# DDR3_LoongSon.net
KiCad netlist of a schematic drawn in Altium Designer
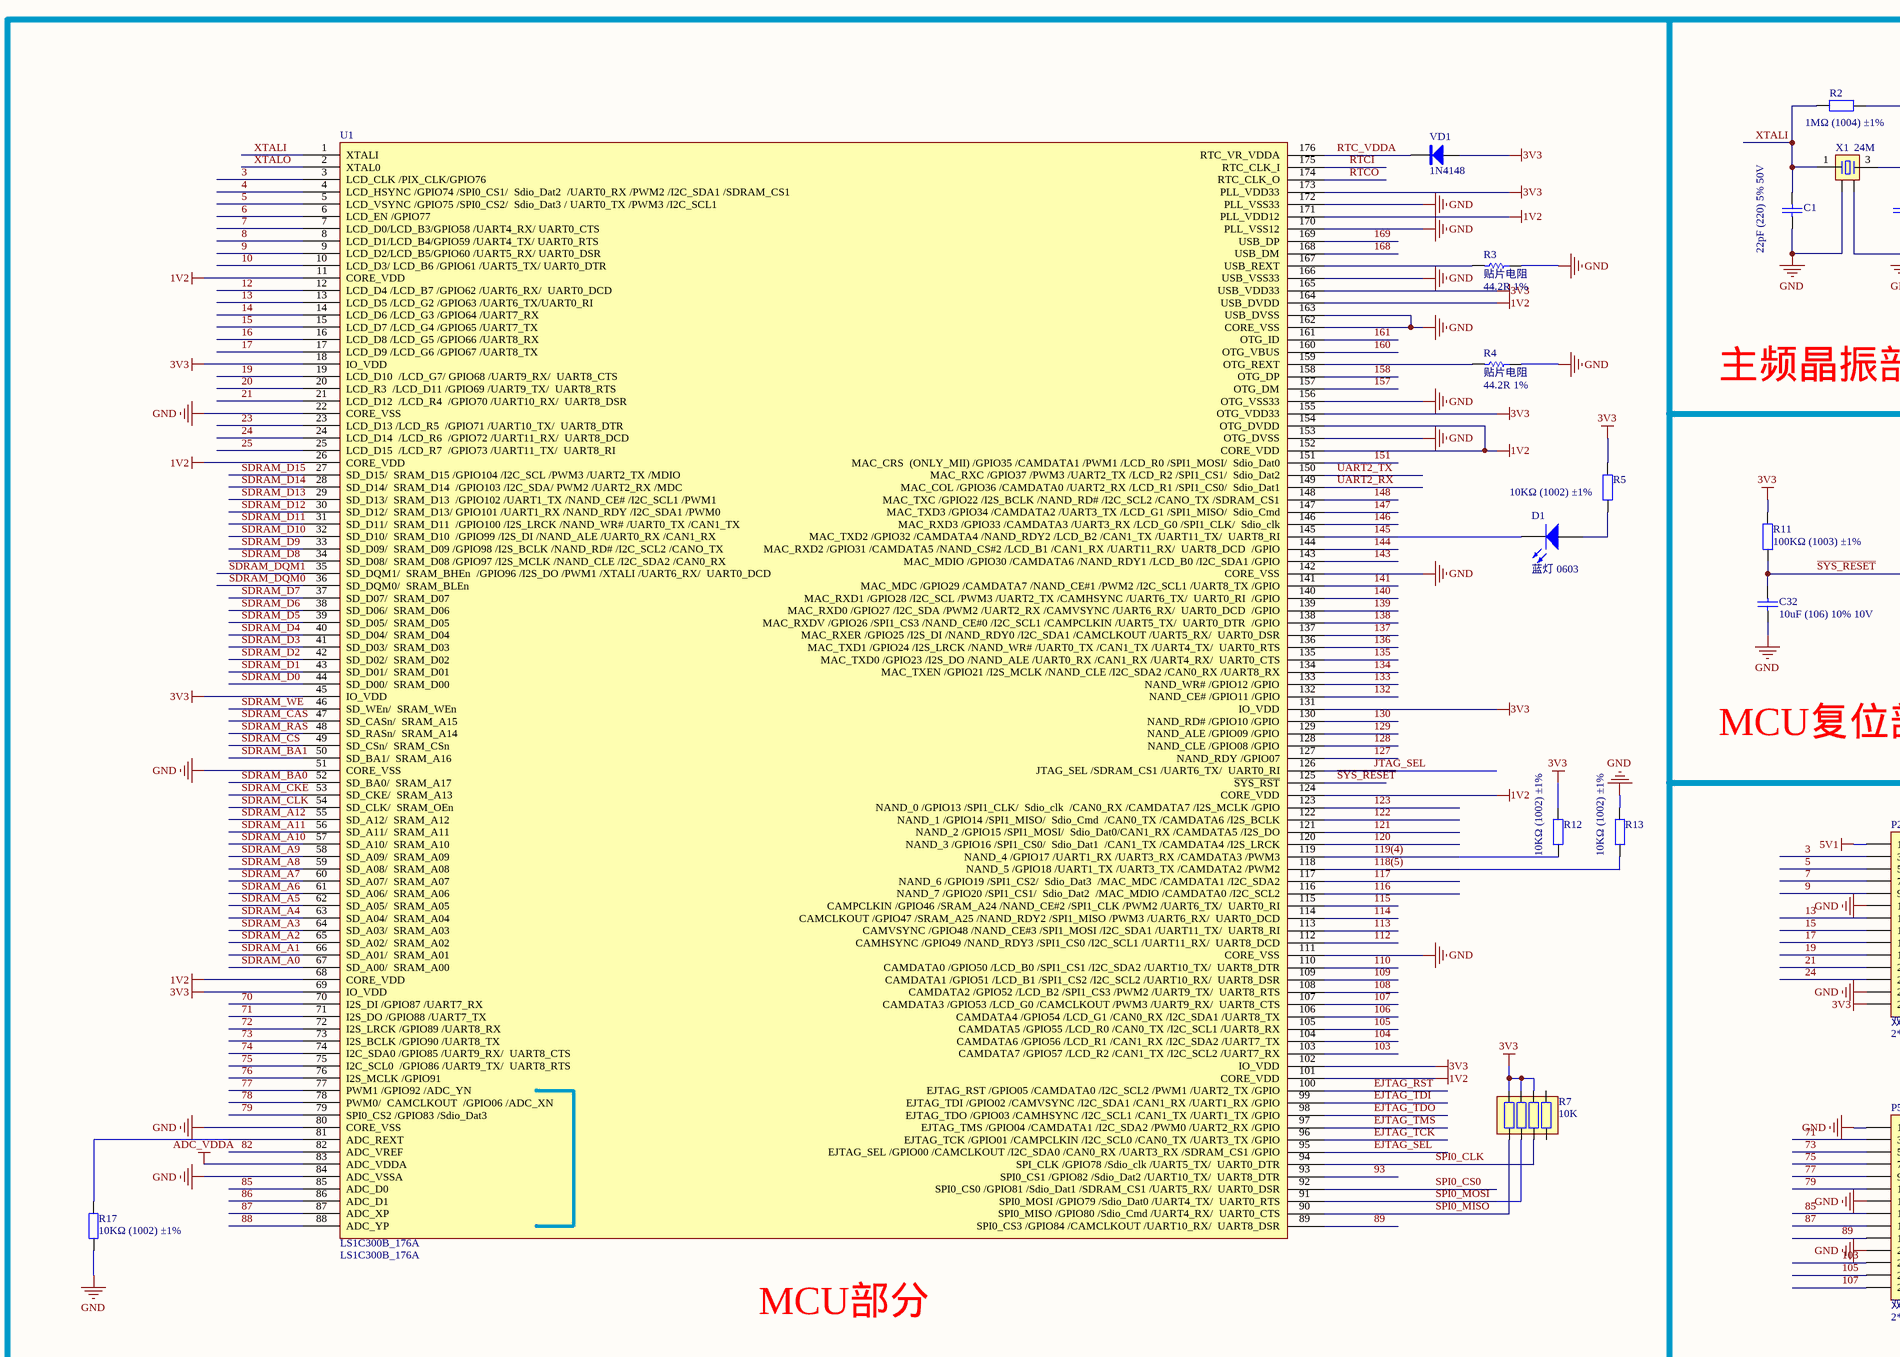
[diagram p0: DDR3_LoongSon.SchDoc, top left]
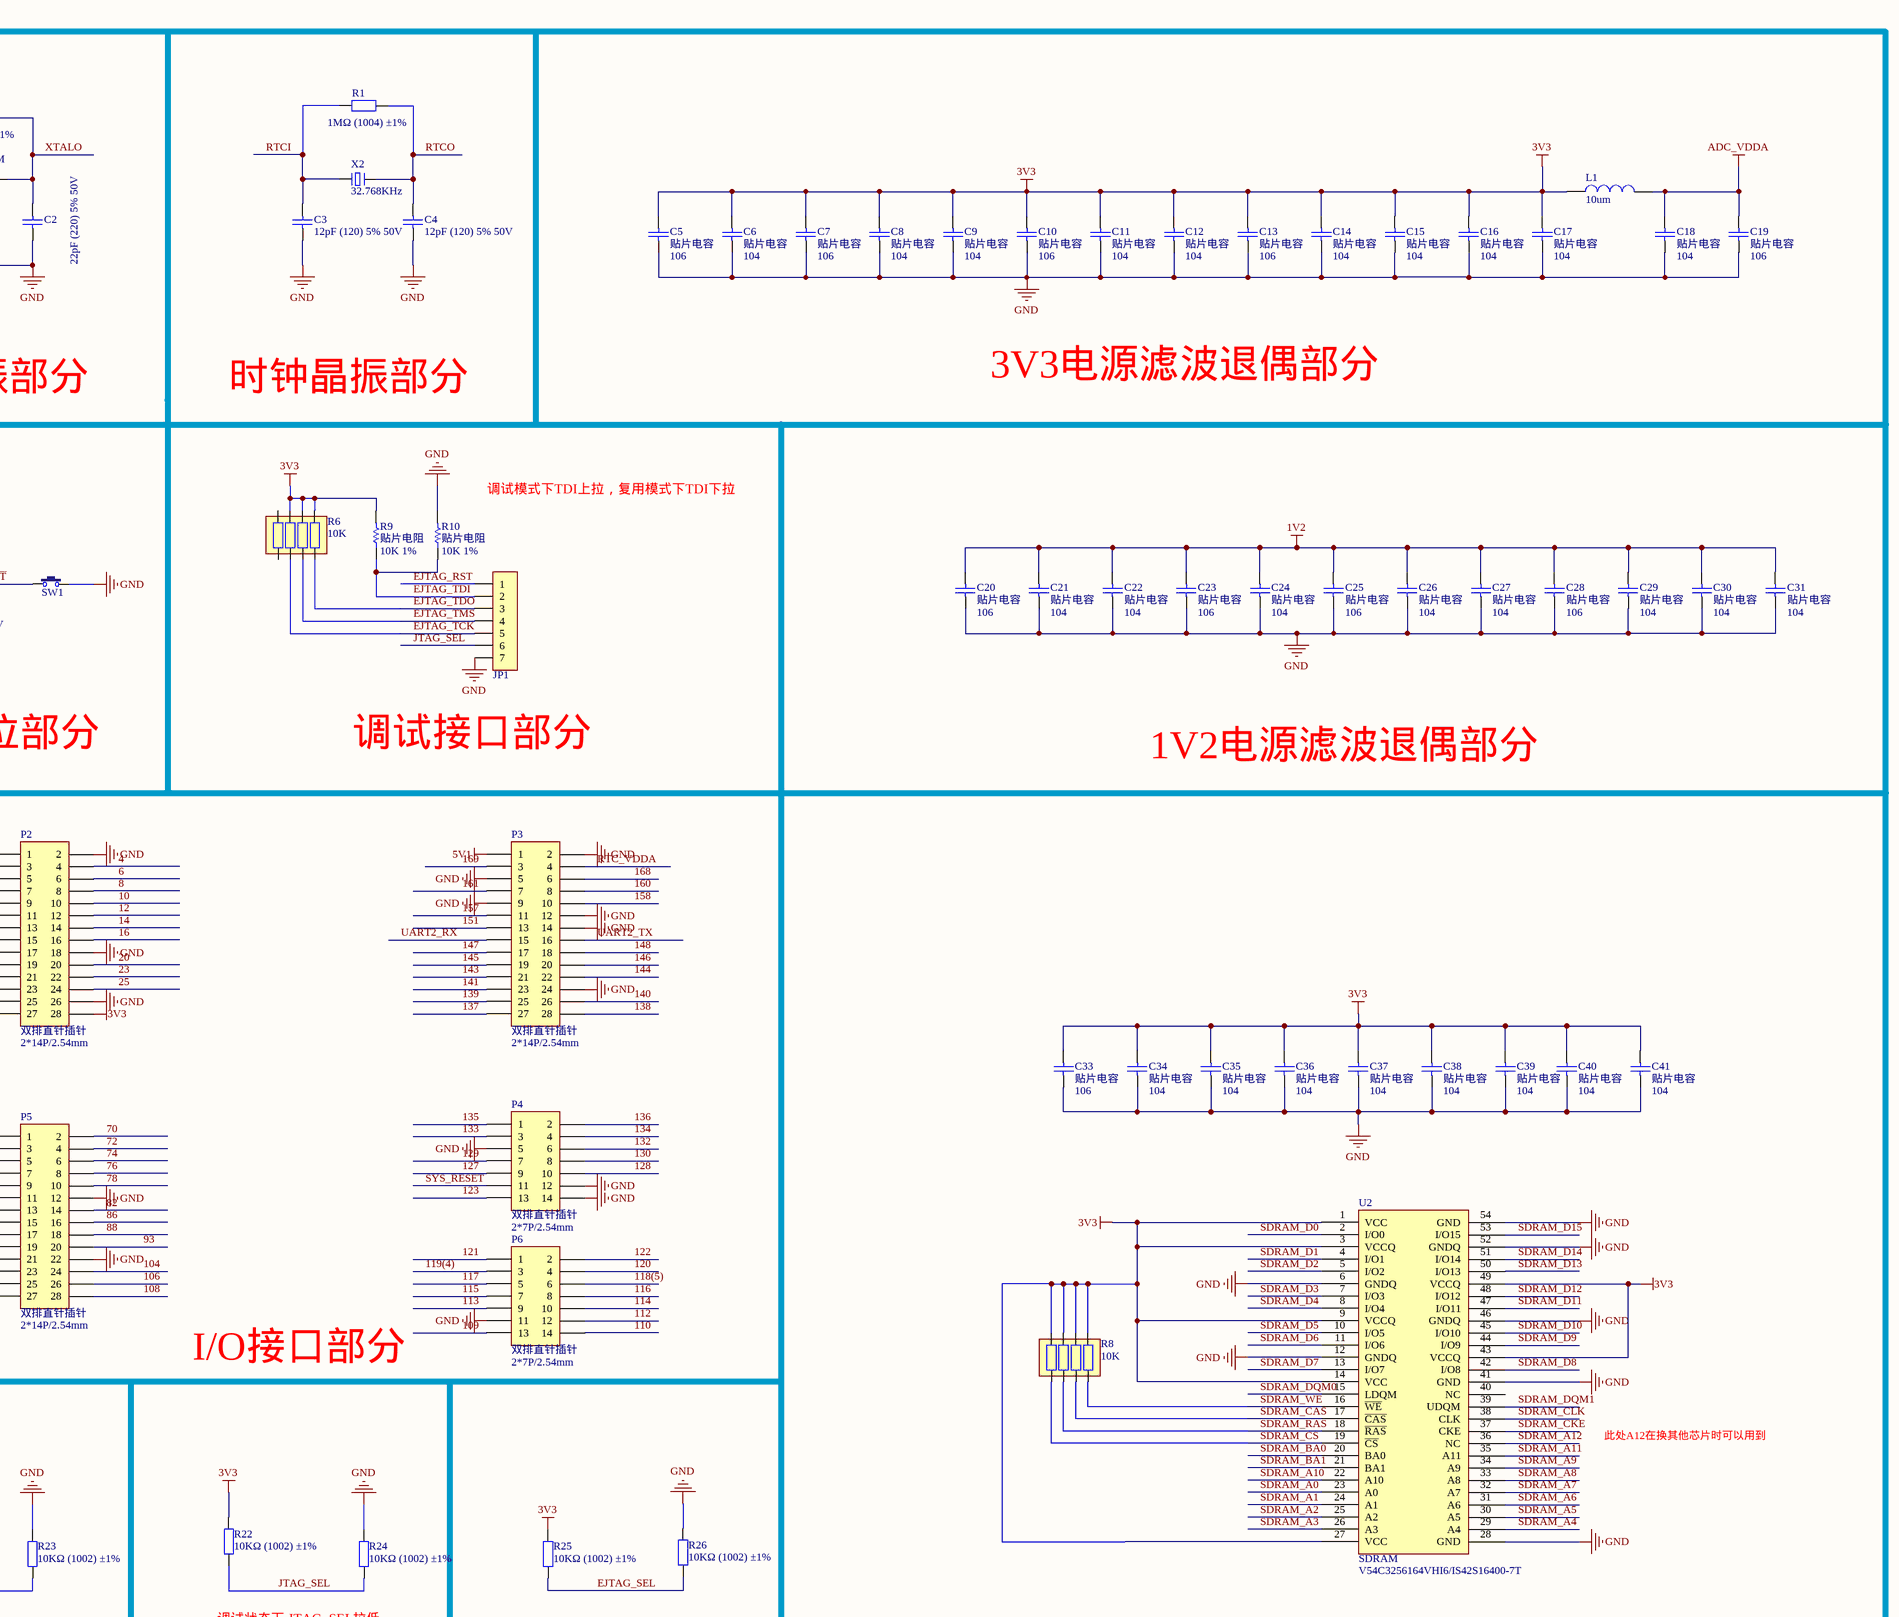
[diagram p1: DDR3_LoongSon.SchDoc, top right]
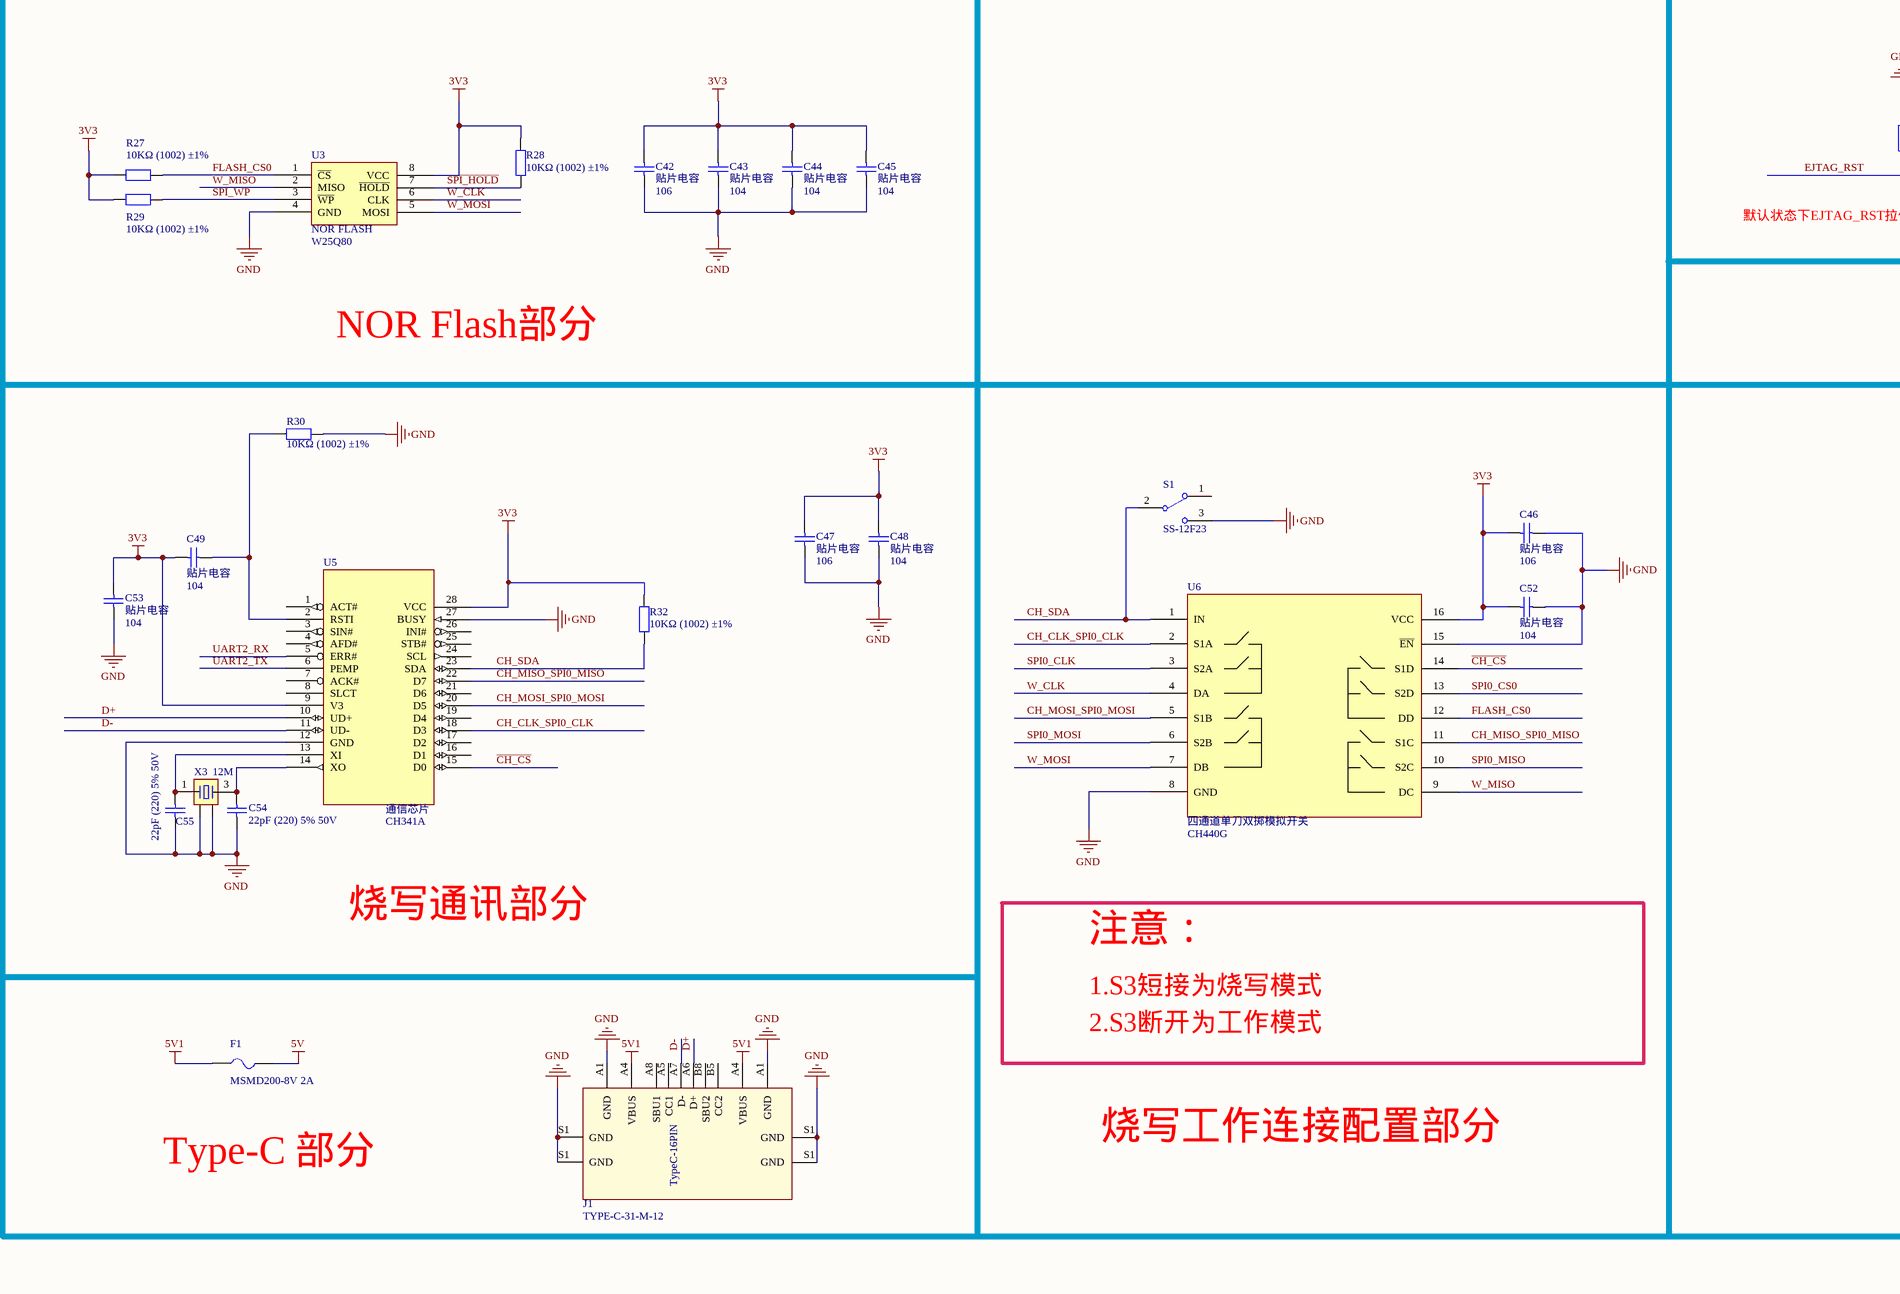
[diagram p2: DDR3_LoongSon.SchDoc, bottom left]
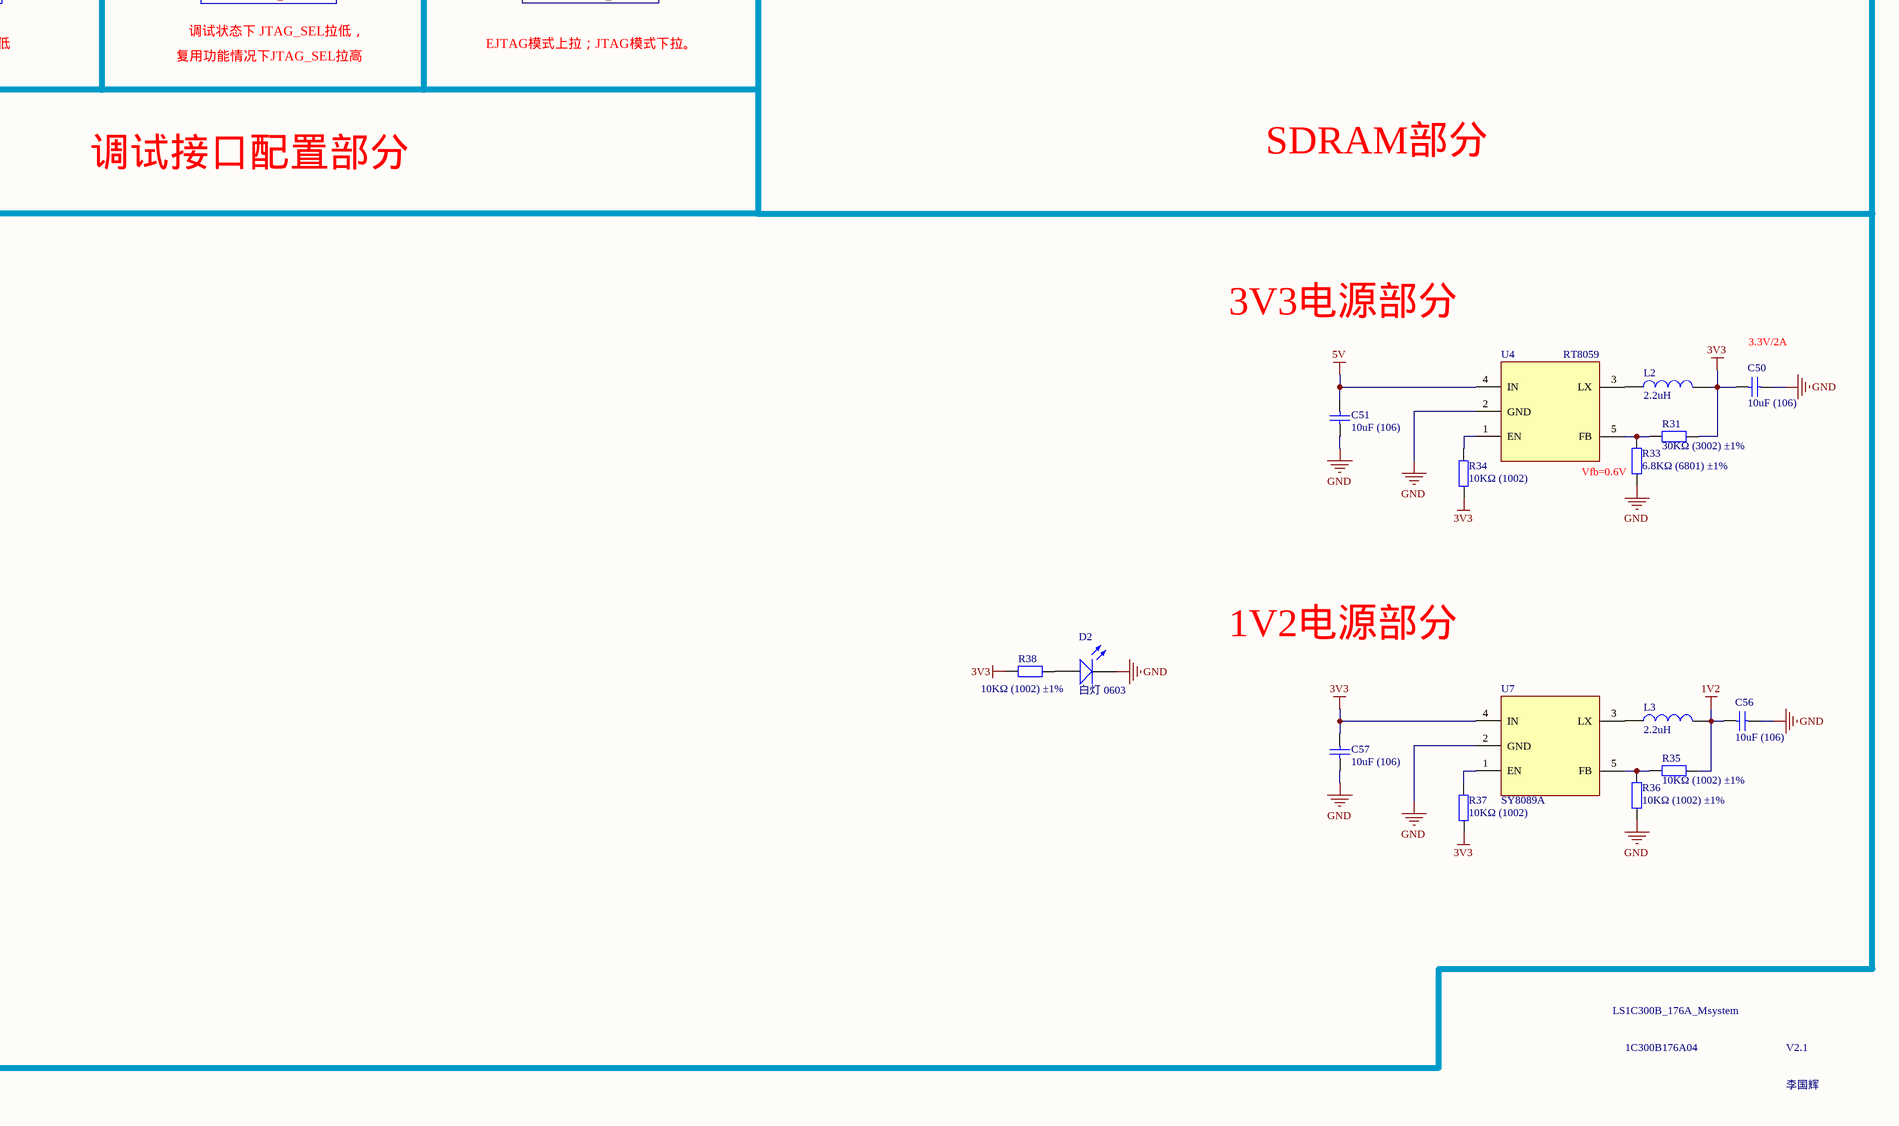
[diagram p3: DDR3_LoongSon.SchDoc, bottom right]

(export (version "E")
  (design (tool "Eeschema 10.0.6"))
  (components
    (comp (ref "C1")
      (value "22pF (220) 5% 50V")
      (footprint "LC-0603_C")
      (description "贴片电容")
      (libsource (lib "Miscellaneous Devices LC") (part "0603 22pF (220) 5% 50V"))
    )
    (comp (ref "C2")
      (value "22pF (220) 5% 50V")
      (footprint "LC-0603_C")
      (description "贴片电容")
      (libsource (lib "Miscellaneous Devices LC") (part "0603 22pF (220) 5% 50V"))
    )
    (comp (ref "C3")
      (value "12pF (120) 5% 50V")
      (footprint "LC-0603_C")
      (description "贴片电容")
      (libsource (lib "Miscellaneous Devices LC") (part "0603 12pF (120) 5% 50V"))
    )
    (comp (ref "C4")
      (value "12pF (120) 5% 50V")
      (footprint "LC-0603_C")
      (description "贴片电容")
      (libsource (lib "Miscellaneous Devices LC") (part "0603 12pF (120) 5% 50V"))
    )
    (comp (ref "C5")
      (value "贴片电容")
      (footprint "LC-0603_C")
      (description "Capacitor")
      (fields (field (name "ALTIUM_VALUE") "106") (field (name "PUBLISHER") "Altium Limited"))
      (libsource (lib "Miscellaneous Devices") (part "Cap"))
    )
    (comp (ref "C6")
      (value "贴片电容")
      (footprint "LC-0603_C")
      (description "Capacitor")
      (fields (field (name "ALTIUM_VALUE") "104") (field (name "PUBLISHER") "Altium Limited"))
      (libsource (lib "Miscellaneous Devices") (part "Cap"))
    )
    (comp (ref "C7")
      (value "贴片电容")
      (footprint "LC-0603_C")
      (description "Capacitor")
      (fields (field (name "ALTIUM_VALUE") "106") (field (name "PUBLISHER") "Altium Limited"))
      (libsource (lib "Miscellaneous Devices") (part "Cap"))
    )
    (comp (ref "C8")
      (value "贴片电容")
      (footprint "LC-0603_C")
      (description "Capacitor")
      (fields (field (name "ALTIUM_VALUE") "104") (field (name "PUBLISHER") "Altium Limited"))
      (libsource (lib "Miscellaneous Devices") (part "Cap"))
    )
    (comp (ref "C9")
      (value "贴片电容")
      (footprint "LC-0603_C")
      (description "Capacitor")
      (fields (field (name "ALTIUM_VALUE") "104") (field (name "PUBLISHER") "Altium Limited"))
      (libsource (lib "Miscellaneous Devices") (part "Cap"))
    )
    (comp (ref "C10")
      (value "贴片电容")
      (footprint "LC-0603_C")
      (description "Capacitor")
      (fields (field (name "ALTIUM_VALUE") "106") (field (name "PUBLISHER") "Altium Limited"))
      (libsource (lib "Miscellaneous Devices") (part "Cap"))
    )
    (comp (ref "C11")
      (value "贴片电容")
      (footprint "LC-0603_C")
      (description "Capacitor")
      (fields (field (name "ALTIUM_VALUE") "104") (field (name "PUBLISHER") "Altium Limited"))
      (libsource (lib "Miscellaneous Devices") (part "Cap"))
    )
    (comp (ref "C12")
      (value "贴片电容")
      (footprint "LC-0603_C")
      (description "Capacitor")
      (fields (field (name "ALTIUM_VALUE") "104") (field (name "PUBLISHER") "Altium Limited"))
      (libsource (lib "Miscellaneous Devices") (part "Cap"))
    )
    (comp (ref "C13")
      (value "贴片电容")
      (footprint "LC-0603_C")
      (description "Capacitor")
      (fields (field (name "ALTIUM_VALUE") "106") (field (name "PUBLISHER") "Altium Limited"))
      (libsource (lib "Miscellaneous Devices") (part "Cap"))
    )
    (comp (ref "C14")
      (value "贴片电容")
      (footprint "LC-0603_C")
      (description "Capacitor")
      (fields (field (name "ALTIUM_VALUE") "104") (field (name "PUBLISHER") "Altium Limited"))
      (libsource (lib "Miscellaneous Devices") (part "Cap"))
    )
    (comp (ref "C15")
      (value "贴片电容")
      (footprint "LC-0603_C")
      (description "Capacitor")
      (fields (field (name "ALTIUM_VALUE") "104") (field (name "PUBLISHER") "Altium Limited"))
      (libsource (lib "Miscellaneous Devices") (part "Cap"))
    )
    (comp (ref "C16")
      (value "贴片电容")
      (footprint "LC-0603_C")
      (description "Capacitor")
      (fields (field (name "ALTIUM_VALUE") "104") (field (name "PUBLISHER") "Altium Limited"))
      (libsource (lib "Miscellaneous Devices") (part "Cap"))
    )
    (comp (ref "C17")
      (value "贴片电容")
      (footprint "LC-0603_C")
      (description "Capacitor")
      (fields (field (name "ALTIUM_VALUE") "104") (field (name "PUBLISHER") "Altium Limited"))
      (libsource (lib "Miscellaneous Devices") (part "Cap"))
    )
    (comp (ref "C18")
      (value "贴片电容")
      (footprint "LC-0603_C")
      (description "Capacitor")
      (fields (field (name "ALTIUM_VALUE") "104") (field (name "PUBLISHER") "Altium Limited"))
      (libsource (lib "Miscellaneous Devices") (part "Cap"))
    )
    (comp (ref "C19")
      (value "贴片电容")
      (footprint "LC-0603_C")
      (description "Capacitor")
      (fields (field (name "ALTIUM_VALUE") "106") (field (name "PUBLISHER") "Altium Limited"))
      (libsource (lib "Miscellaneous Devices") (part "Cap"))
    )
    (comp (ref "C20")
      (value "贴片电容")
      (footprint "LC-0603_C")
      (description "Capacitor")
      (fields (field (name "ALTIUM_VALUE") "106") (field (name "PUBLISHER") "Altium Limited"))
      (libsource (lib "Miscellaneous Devices") (part "Cap"))
    )
    (comp (ref "C21")
      (value "贴片电容")
      (footprint "LC-0603_C")
      (description "Capacitor")
      (fields (field (name "ALTIUM_VALUE") "104") (field (name "PUBLISHER") "Altium Limited"))
      (libsource (lib "Miscellaneous Devices") (part "Cap"))
    )
    (comp (ref "C22")
      (value "贴片电容")
      (footprint "LC-0603_C")
      (description "Capacitor")
      (fields (field (name "ALTIUM_VALUE") "104") (field (name "PUBLISHER") "Altium Limited"))
      (libsource (lib "Miscellaneous Devices") (part "Cap"))
    )
    (comp (ref "C23")
      (value "贴片电容")
      (footprint "LC-0603_C")
      (description "Capacitor")
      (fields (field (name "ALTIUM_VALUE") "106") (field (name "PUBLISHER") "Altium Limited"))
      (libsource (lib "Miscellaneous Devices") (part "Cap"))
    )
    (comp (ref "C24")
      (value "贴片电容")
      (footprint "LC-0603_C")
      (description "Capacitor")
      (fields (field (name "ALTIUM_VALUE") "104") (field (name "PUBLISHER") "Altium Limited"))
      (libsource (lib "Miscellaneous Devices") (part "Cap"))
    )
    (comp (ref "C25")
      (value "贴片电容")
      (footprint "LC-0603_C")
      (description "Capacitor")
      (fields (field (name "ALTIUM_VALUE") "106") (field (name "PUBLISHER") "Altium Limited"))
      (libsource (lib "Miscellaneous Devices") (part "Cap"))
    )
    (comp (ref "C26")
      (value "贴片电容")
      (footprint "LC-0603_C")
      (description "Capacitor")
      (fields (field (name "ALTIUM_VALUE") "104") (field (name "PUBLISHER") "Altium Limited"))
      (libsource (lib "Miscellaneous Devices") (part "Cap"))
    )
    (comp (ref "C27")
      (value "贴片电容")
      (footprint "LC-0603_C")
      (description "Capacitor")
      (fields (field (name "ALTIUM_VALUE") "104") (field (name "PUBLISHER") "Altium Limited"))
      (libsource (lib "Miscellaneous Devices") (part "Cap"))
    )
    (comp (ref "C28")
      (value "贴片电容")
      (footprint "LC-0603_C")
      (description "Capacitor")
      (fields (field (name "ALTIUM_VALUE") "106") (field (name "PUBLISHER") "Altium Limited"))
      (libsource (lib "Miscellaneous Devices") (part "Cap"))
    )
    (comp (ref "C29")
      (value "贴片电容")
      (footprint "LC-0603_C")
      (description "Capacitor")
      (fields (field (name "ALTIUM_VALUE") "104") (field (name "PUBLISHER") "Altium Limited"))
      (libsource (lib "Miscellaneous Devices") (part "Cap"))
    )
    (comp (ref "C30")
      (value "贴片电容")
      (footprint "LC-0603_C")
      (description "Capacitor")
      (fields (field (name "ALTIUM_VALUE") "104") (field (name "PUBLISHER") "Altium Limited"))
      (libsource (lib "Miscellaneous Devices") (part "Cap"))
    )
    (comp (ref "C31")
      (value "贴片电容")
      (footprint "LC-0603_C")
      (description "Capacitor")
      (fields (field (name "ALTIUM_VALUE") "104") (field (name "PUBLISHER") "Altium Limited"))
      (libsource (lib "Miscellaneous Devices") (part "Cap"))
    )
    (comp (ref "C32")
      (value "10uF (106) 10% 10V")
      (footprint "LC-0603_C")
      (description "贴片电容")
      (libsource (lib "Miscellaneous Devices LC") (part "0603 10uF (106) 10% 10V"))
    )
    (comp (ref "C33")
      (value "贴片电容")
      (footprint "LC-0603_C")
      (description "Capacitor")
      (fields (field (name "ALTIUM_VALUE") "106") (field (name "PUBLISHER") "Altium Limited"))
      (libsource (lib "Miscellaneous Devices") (part "Cap"))
    )
    (comp (ref "C34")
      (value "贴片电容")
      (footprint "LC-0603_C")
      (description "Capacitor")
      (fields (field (name "ALTIUM_VALUE") "104") (field (name "PUBLISHER") "Altium Limited"))
      (libsource (lib "Miscellaneous Devices") (part "Cap"))
    )
    (comp (ref "C35")
      (value "贴片电容")
      (footprint "LC-0603_C")
      (description "Capacitor")
      (fields (field (name "ALTIUM_VALUE") "104") (field (name "PUBLISHER") "Altium Limited"))
      (libsource (lib "Miscellaneous Devices") (part "Cap"))
    )
    (comp (ref "C36")
      (value "贴片电容")
      (footprint "LC-0603_C")
      (description "Capacitor")
      (fields (field (name "ALTIUM_VALUE") "104") (field (name "PUBLISHER") "Altium Limited"))
      (libsource (lib "Miscellaneous Devices") (part "Cap"))
    )
    (comp (ref "C37")
      (value "贴片电容")
      (footprint "LC-0603_C")
      (description "Capacitor")
      (fields (field (name "ALTIUM_VALUE") "104") (field (name "PUBLISHER") "Altium Limited"))
      (libsource (lib "Miscellaneous Devices") (part "Cap"))
    )
    (comp (ref "C38")
      (value "贴片电容")
      (footprint "LC-0603_C")
      (description "Capacitor")
      (fields (field (name "ALTIUM_VALUE") "104") (field (name "PUBLISHER") "Altium Limited"))
      (libsource (lib "Miscellaneous Devices") (part "Cap"))
    )
    (comp (ref "C39")
      (value "贴片电容")
      (footprint "LC-0603_C")
      (description "Capacitor")
      (fields (field (name "ALTIUM_VALUE") "104") (field (name "PUBLISHER") "Altium Limited"))
      (libsource (lib "Miscellaneous Devices") (part "Cap"))
    )
    (comp (ref "C40")
      (value "贴片电容")
      (footprint "LC-0603_C")
      (description "Capacitor")
      (fields (field (name "ALTIUM_VALUE") "104") (field (name "PUBLISHER") "Altium Limited"))
      (libsource (lib "Miscellaneous Devices") (part "Cap"))
    )
    (comp (ref "C41")
      (value "贴片电容")
      (footprint "LC-0603_C")
      (description "Capacitor")
      (fields (field (name "ALTIUM_VALUE") "104") (field (name "PUBLISHER") "Altium Limited"))
      (libsource (lib "Miscellaneous Devices") (part "Cap"))
    )
    (comp (ref "C42")
      (value "贴片电容")
      (footprint "LC-0603_C")
      (description "Capacitor")
      (fields (field (name "ALTIUM_VALUE") "106") (field (name "PUBLISHER") "Altium Limited"))
      (libsource (lib "Miscellaneous Devices") (part "Cap"))
    )
    (comp (ref "C43")
      (value "贴片电容")
      (footprint "LC-0603_C")
      (description "Capacitor")
      (fields (field (name "ALTIUM_VALUE") "104") (field (name "PUBLISHER") "Altium Limited"))
      (libsource (lib "Miscellaneous Devices") (part "Cap"))
    )
    (comp (ref "C44")
      (value "贴片电容")
      (footprint "LC-0603_C")
      (description "Capacitor")
      (fields (field (name "ALTIUM_VALUE") "104") (field (name "PUBLISHER") "Altium Limited"))
      (libsource (lib "Miscellaneous Devices") (part "Cap"))
    )
    (comp (ref "C45")
      (value "贴片电容")
      (footprint "LC-0603_C")
      (description "Capacitor")
      (fields (field (name "ALTIUM_VALUE") "104") (field (name "PUBLISHER") "Altium Limited"))
      (libsource (lib "Miscellaneous Devices") (part "Cap"))
    )
    (comp (ref "C46")
      (value "贴片电容")
      (footprint "LC-0603_C")
      (description "Capacitor")
      (fields (field (name "ALTIUM_VALUE") "106") (field (name "PUBLISHER") "Altium Limited"))
      (libsource (lib "Miscellaneous Devices") (part "Cap"))
    )
    (comp (ref "C47")
      (value "贴片电容")
      (footprint "LC-0603_C")
      (description "Capacitor")
      (fields (field (name "ALTIUM_VALUE") "106") (field (name "PUBLISHER") "Altium Limited"))
      (libsource (lib "Miscellaneous Devices") (part "Cap"))
    )
    (comp (ref "C48")
      (value "贴片电容")
      (footprint "LC-0603_C")
      (description "Capacitor")
      (fields (field (name "ALTIUM_VALUE") "104") (field (name "PUBLISHER") "Altium Limited"))
      (libsource (lib "Miscellaneous Devices") (part "Cap"))
    )
    (comp (ref "C49")
      (value "贴片电容")
      (footprint "LC-0603_C")
      (description "Capacitor")
      (fields (field (name "ALTIUM_VALUE") "104") (field (name "PUBLISHER") "Altium Limited"))
      (libsource (lib "Miscellaneous Devices") (part "Cap"))
    )
    (comp (ref "C50")
      (value "10uF (106)")
      (footprint "LC-0603_C")
      (description "贴片电容")
      (libsource (lib "Miscellaneous Devices LC") (part "0603 10uF (106) 10% 10V"))
    )
    (comp (ref "C51")
      (value "10uF (106)")
      (footprint "LC-0603_C")
      (description "贴片电容")
      (libsource (lib "Miscellaneous Devices LC") (part "0603 10uF (106) 10% 10V"))
    )
    (comp (ref "C52")
      (value "贴片电容")
      (footprint "LC-0603_C")
      (description "Capacitor")
      (fields (field (name "ALTIUM_VALUE") "104") (field (name "PUBLISHER") "Altium Limited"))
      (libsource (lib "Miscellaneous Devices") (part "Cap"))
    )
    (comp (ref "C53")
      (value "贴片电容")
      (footprint "LC-0603_C")
      (description "Capacitor")
      (fields (field (name "ALTIUM_VALUE") "104") (field (name "PUBLISHER") "Altium Limited"))
      (libsource (lib "Miscellaneous Devices") (part "Cap"))
    )
    (comp (ref "C54")
      (value "22pF (220) 5% 50V")
      (footprint "LC-0603_C")
      (description "贴片电容")
      (libsource (lib "Miscellaneous Devices LC") (part "0603 22pF (220) 5% 50V"))
    )
    (comp (ref "C55")
      (value "22pF (220) 5% 50V")
      (footprint "LC-0603_C")
      (description "贴片电容")
      (libsource (lib "Miscellaneous Devices LC") (part "0603 22pF (220) 5% 50V"))
    )
    (comp (ref "C56")
      (value "10uF (106)")
      (footprint "LC-0603_C")
      (description "贴片电容")
      (libsource (lib "Miscellaneous Devices LC") (part "0603 10uF (106) 10% 10V"))
    )
    (comp (ref "C57")
      (value "10uF (106)")
      (footprint "LC-0603_C")
      (description "贴片电容")
      (libsource (lib "Miscellaneous Devices LC") (part "0603 10uF (106) 10% 10V"))
    )
    (comp (ref "D1")
      (value "蓝灯 0603")
      (footprint "LC-0603_LED_S1")
      (description "发光二极管")
      (libsource (lib "Miscellaneous Devices LC") (part "0603 蓝灯"))
    )
    (comp (ref "D2")
      (value "白灯 0603")
      (footprint "LC-0603_LED_S1")
      (description "发光二极管")
      (libsource (lib "Miscellaneous Devices LC") (part "0603 白灯"))
    )
    (comp (ref "F1")
      (value "MSMD200-8V 2A")
      (footprint "FU 1206")
      (description "贴片保险丝")
      (fields (field (name "版权归属") "源创客"))
      (libsource (lib "保险丝-晶振") (part "FU"))
    )
    (comp (ref "J1")
      (value "TYPE-C-31-M-12")
      (footprint "TYPE-C-31-M-12")
      (libsource (lib "Type-C") (part "TYPE-C-31-M-12"))
    )
    (comp (ref "JP1")
      (value "HDR-1X7")
      (footprint "HDR-1X7")
      (description "7P接插件")
      (fields (field (name "版权归属") "源创客"))
      (libsource (lib "接插件") (part "Header 7"))
    )
    (comp (ref "L1")
      (value "10um")
      (footprint "L 0603")
      (description "小功率贴片电感")
      (fields (field (name "版权归属") "源创客"))
      (libsource (lib "电阻-电容-电感") (part "L"))
    )
    (comp (ref "L2")
      (value "2.2uH")
      (footprint "2520-L")
      (description "小功率贴片电感")
      (fields (field (name "版权归属") "源创客"))
      (libsource (lib "电阻-电容-电感") (part "L"))
    )
    (comp (ref "L3")
      (value "2.2uH")
      (footprint "2520-L")
      (description "小功率贴片电感")
      (fields (field (name "版权归属") "源创客"))
      (libsource (lib "电阻-电容-电感") (part "L"))
    )
    (comp (ref "P2")
      (value "双排直针插针")
      (footprint "HDR2X14")
      (description "Header, 14-Pin, Dual row")
      (fields (field (name "ALTIUM_VALUE") "2*14P/2.54mm") (field (name "PUBLISHER") "Altium Limited"))
      (libsource (lib "Miscellaneous Connectors") (part "MHDR2X14"))
    )
    (comp (ref "P3")
      (value "双排直针插针")
      (footprint "HDR2X14")
      (description "Header, 14-Pin, Dual row")
      (fields (field (name "ALTIUM_VALUE") "2*14P/2.54mm") (field (name "PUBLISHER") "Altium Limited"))
      (libsource (lib "Miscellaneous Connectors") (part "MHDR2X14"))
    )
    (comp (ref "P4")
      (value "双排直针插针")
      (footprint "HDR2X7")
      (description "Header, 7-Pin, Dual row")
      (fields (field (name "ALTIUM_VALUE") "2*7P/2.54mm") (field (name "PUBLISHER") "Altium Limited"))
      (libsource (lib "Miscellaneous Connectors") (part "MHDR2X7"))
    )
    (comp (ref "P5")
      (value "双排直针插针")
      (footprint "HDR2X14")
      (description "Header, 14-Pin, Dual row")
      (fields (field (name "ALTIUM_VALUE") "2*14P/2.54mm") (field (name "PUBLISHER") "Altium Limited"))
      (libsource (lib "Miscellaneous Connectors") (part "MHDR2X14"))
    )
    (comp (ref "P6")
      (value "双排直针插针")
      (footprint "HDR2X7")
      (description "Header, 7-Pin, Dual row")
      (fields (field (name "ALTIUM_VALUE") "2*7P/2.54mm") (field (name "PUBLISHER") "Altium Limited"))
      (libsource (lib "Miscellaneous Connectors") (part "MHDR2X7"))
    )
    (comp (ref "R1")
      (value "1MΩ (1004) ±1%")
      (footprint "LC-0603_R")
      (description "贴片电阻")
      (libsource (lib "Miscellaneous Devices LC") (part "0603 1MΩ (1004) 1%"))
    )
    (comp (ref "R2")
      (value "1MΩ (1004) ±1%")
      (footprint "LC-0603_R")
      (description "贴片电阻")
      (libsource (lib "Miscellaneous Devices LC") (part "0603 1MΩ (1004) 1%"))
    )
    (comp (ref "R3")
      (value "贴片电阻")
      (footprint "LC-0603_R")
      (description "Resistor")
      (fields (field (name "ALTIUM_VALUE") "44.2R 1%") (field (name "PUBLISHER") "Altium Limited"))
      (libsource (lib "Miscellaneous Devices") (part "Res1"))
    )
    (comp (ref "R4")
      (value "贴片电阻")
      (footprint "LC-0603_R")
      (description "Resistor")
      (fields (field (name "ALTIUM_VALUE") "44.2R 1%") (field (name "PUBLISHER") "Altium Limited"))
      (libsource (lib "Miscellaneous Devices") (part "Res1"))
    )
    (comp (ref "R5")
      (value "10KΩ (1002) ±1%")
      (footprint "LC-0603_R")
      (description "贴片电阻")
      (libsource (lib "") (part "0603 10KΩ (1002) 1%_1"))
    )
    (comp (ref "R6")
      (value "10K")
      (footprint "RCA-8P4R-0603")
      (description "贴片网络排阻")
      (fields (field (name "版权归属") "源创客"))
      (libsource (lib "电阻-电容-电感") (part "R-8P4R"))
    )
    (comp (ref "R7")
      (value "10K")
      (footprint "RCA-8P4R-0603")
      (description "贴片网络排阻")
      (fields (field (name "版权归属") "源创客"))
      (libsource (lib "电阻-电容-电感") (part "R-8P4R"))
    )
    (comp (ref "R8")
      (value "10K")
      (footprint "RCA-8P4R-0603")
      (description "贴片网络排阻")
      (fields (field (name "版权归属") "源创客"))
      (libsource (lib "电阻-电容-电感") (part "R-8P4R"))
    )
    (comp (ref "R9")
      (value "贴片电阻")
      (footprint "LC-0603_R")
      (description "Resistor")
      (fields (field (name "ALTIUM_VALUE") "10K 1%") (field (name "PUBLISHER") "Altium Limited"))
      (libsource (lib "Miscellaneous Devices") (part "Res1"))
    )
    (comp (ref "R10")
      (value "贴片电阻")
      (footprint "LC-0603_R")
      (description "Resistor")
      (fields (field (name "ALTIUM_VALUE") "10K 1%") (field (name "PUBLISHER") "Altium Limited"))
      (libsource (lib "Miscellaneous Devices") (part "Res1"))
    )
    (comp (ref "R11")
      (value "100KΩ (1003) ±1%")
      (footprint "LC-0603_R")
      (description "贴片电阻")
      (libsource (lib "Miscellaneous Devices LC") (part "0603 100KΩ (1003) 1%"))
    )
    (comp (ref "R12")
      (value "10KΩ (1002) ±1%")
      (footprint "LC-0603_R")
      (description "贴片电阻")
      (libsource (lib "") (part "0603 10KΩ (1002) 1%_1"))
    )
    (comp (ref "R13")
      (value "10KΩ (1002) ±1%")
      (footprint "LC-0603_R")
      (description "贴片电阻")
      (libsource (lib "") (part "0603 10KΩ (1002) 1%_1"))
    )
    (comp (ref "R17")
      (value "10KΩ (1002) ±1%")
      (footprint "LC-0603_R")
      (description "贴片电阻")
      (libsource (lib "") (part "0603 10KΩ (1002) 1%_1"))
    )
    (comp (ref "R22")
      (value "10KΩ (1002) ±1%")
      (footprint "LC-0603_R")
      (description "贴片电阻")
      (libsource (lib "") (part "0603 10KΩ (1002) 1%_1"))
    )
    (comp (ref "R23")
      (value "10KΩ (1002) ±1%")
      (footprint "LC-0603_R")
      (description "贴片电阻")
      (libsource (lib "") (part "0603 10KΩ (1002) 1%_1"))
    )
    (comp (ref "R24")
      (value "10KΩ (1002) ±1%")
      (footprint "LC-0603_R")
      (description "贴片电阻")
      (libsource (lib "") (part "0603 10KΩ (1002) 1%_1"))
    )
    (comp (ref "R25")
      (value "10KΩ (1002) ±1%")
      (footprint "LC-0603_R")
      (description "贴片电阻")
      (libsource (lib "") (part "0603 10KΩ (1002) 1%_1"))
    )
    (comp (ref "R26")
      (value "10KΩ (1002) ±1%")
      (footprint "LC-0603_R")
      (description "贴片电阻")
      (libsource (lib "") (part "0603 10KΩ (1002) 1%_1"))
    )
    (comp (ref "R27")
      (value "10KΩ (1002) ±1%")
      (footprint "LC-0603_R")
      (description "贴片电阻")
      (libsource (lib "Miscellaneous Devices LC") (part "0603 10KΩ (1002) 1%"))
    )
    (comp (ref "R28")
      (value "10KΩ (1002) ±1%")
      (footprint "LC-0603_R")
      (description "贴片电阻")
      (libsource (lib "") (part "0603 10KΩ (1002) 1%_1"))
    )
    (comp (ref "R29")
      (value "10KΩ (1002) ±1%")
      (footprint "LC-0603_R")
      (description "贴片电阻")
      (libsource (lib "Miscellaneous Devices LC") (part "0603 10KΩ (1002) 1%"))
    )
    (comp (ref "R30")
      (value "10KΩ (1002) ±1%")
      (footprint "LC-0603_R")
      (description "贴片电阻")
      (libsource (lib "Miscellaneous Devices LC") (part "0603 10KΩ (1002) 1%"))
    )
    (comp (ref "R31")
      (value "30KΩ (3002) ±1%")
      (footprint "LC-0603_R")
      (description "贴片电阻")
      (libsource (lib "Miscellaneous Devices LC") (part "0603 30KΩ (3002) 1%"))
    )
    (comp (ref "R32")
      (value "10KΩ (1002) ±1%")
      (footprint "LC-0603_R")
      (description "贴片电阻")
      (libsource (lib "") (part "0603 10KΩ (1002) 1%_1"))
    )
    (comp (ref "R33")
      (value "6.8KΩ (6801) ±1%")
      (footprint "LC-0603_R")
      (description "贴片电阻")
      (libsource (lib "Miscellaneous Devices LC") (part "0603 6.8KΩ (6801) 1%"))
    )
    (comp (ref "R34")
      (value "10KΩ (1002)")
      (footprint "LC-0603_R")
      (description "贴片电阻")
      (libsource (lib "") (part "0603 10KΩ (1002) 1%_1"))
    )
    (comp (ref "R35")
      (value "10KΩ (1002) ±1%")
      (footprint "LC-0603_R")
      (description "贴片电阻")
      (libsource (lib "Miscellaneous Devices LC") (part "0603 10KΩ (1002) 1%"))
    )
    (comp (ref "R36")
      (value "10KΩ (1002) ±1%")
      (footprint "LC-0603_R")
      (description "贴片电阻")
      (libsource (lib "") (part "0603 10KΩ (1002) 1%_1"))
    )
    (comp (ref "R37")
      (value "10KΩ (1002)")
      (footprint "LC-0603_R")
      (description "贴片电阻")
      (libsource (lib "") (part "0603 10KΩ (1002) 1%_1"))
    )
    (comp (ref "R38")
      (value "10KΩ (1002) ±1%")
      (footprint "LC-0603_R")
      (description "贴片电阻")
      (libsource (lib "Miscellaneous Devices LC") (part "0603 10KΩ (1002) 1%"))
    )
    (comp (ref "S1")
      (value "SS-12F23")
      (footprint "MSK-12C01-07")
      (description "1路波动开关")
      (fields (field (name "版权归属") "源创客"))
      (libsource (lib "按键-开关") (part "SSW-1P"))
    )
    (comp (ref "SW1")
      (value "3x6x5")
      (footprint "TSW SMD-3*6*2.5")
      (description "3x6轻触开关")
      (fields (field (name "版权归属") "源创客"))
      (libsource (lib "按键-开关") (part "TSW 3x6"))
    )
    (comp (ref "U1")
      (value "LS1C300B_176A")
      (footprint "QFP176")
      (description "龙芯1C300B QFP176A")
      (fields (field (name "ALTIUM_VALUE") "LS1C300B_176A"))
      (libsource (lib "Type-C") (part "LS1C300B_176A"))
    )
    (comp (ref "U2")
      (value "SDRAM")
      (footprint "TSOP54")
      (description "ISSI 公司SDRAM ， 166, 133, 100 MHz")
      (fields (field (name "ALTIUM_VALUE") "V54C3256164VHI6/IS42S16400-7T"))
      (libsource (lib "Type-C") (part "IS42S16400"))
    )
    (comp (ref "U3")
      (value "NOR FLASH")
      (footprint "SOIC-8-N")
      (description "nor flash W25Q64....华邦")
      (fields (field (name "ALTIUM_VALUE") "W25Q80"))
      (libsource (lib "Type-C") (part "W25Q80BV"))
    )
    (comp (ref "U4")
      (value "RT8059")
      (footprint "SOT23-5N")
      (description "LDO")
      (libsource (lib "Type-C") (part "RT8059"))
    )
    (comp (ref "U5")
      (value "通信芯片")
      (footprint "SOP28")
      (description "USB to Print Port / Parallel")
      (fields (field (name "ALTIUM_VALUE") "CH341A"))
      (libsource (lib "Type-C") (part "CH341A"))
    )
    (comp (ref "U6")
      (value "四通道单刀双掷模拟开关")
      (footprint "SOP-16")
      (description "四通道单刀双掷模拟开关 ，EN 低电平使能，IN 低电平 1#端导通，高电平2#端导通，DX是公共端")
      (fields (field (name "ALTIUM_VALUE") "CH440G"))
      (libsource (lib "LGHLIB") (part "CH440"))
    )
    (comp (ref "U7")
      (value "SY8089A")
      (footprint "SOT23-5N")
      (description "LDO")
      (libsource (lib "Type-C") (part "SY8089A"))
    )
    (comp (ref "VD1")
      (value "1N4148")
      (footprint "MINI_MELF (LL34)")
      (description "高速开关二极管")
      (fields (field (name "版权归属") "源创客"))
      (libsource (lib "二极管-整流桥") (part "1N4148"))
    )
    (comp (ref "X1")
      (value "24M")
      (footprint "XTAL-3225")
      (description "4脚晶振")
      (fields (field (name "版权归属") "源创客"))
      (libsource (lib "保险丝-晶振") (part "XTAL-4"))
    )
    (comp (ref "X2")
      (value "32.768KHz")
      (footprint "XTAL-3215")
      (description "2脚晶振")
      (fields (field (name "版权归属") "源创客"))
      (libsource (lib "保险丝-晶振") (part "XTAL-2"))
    )
    (comp (ref "X3")
      (value "12M")
      (footprint "XTAL-3225")
      (description "4脚晶振")
      (fields (field (name "版权归属") "源创客"))
      (libsource (lib "保险丝-晶振") (part "XTAL-4"))
    )
  )
  (nets
    (net (code "1") (name "/3") (class "Default")
      (node (ref "P2") (pin "3") (pinfunction "3_3") (pintype "passive"))
      (node (ref "U1") (pin "3") (pinfunction "LCD_CLK_/PIX_CLK/GPIO76_3") (pintype "passive"))
    )
    (net (code "2") (name "/4") (class "Default")
      (node (ref "P2") (pin "4") (pinfunction "4_4") (pintype "passive"))
      (node (ref "U1") (pin "4") (pinfunction "LCD_HSYNC_/GPIO74_/SPI0_CS1/__Sdio_Dat2__/UART0_RX_/PWM2_/I2C_SDA1_/SDRAM_CS1_4") (pintype "passive"))
    )
    (net (code "3") (name "/5") (class "Default")
      (node (ref "P2") (pin "5") (pinfunction "5_5") (pintype "passive"))
      (node (ref "U1") (pin "5") (pinfunction "LCD_VSYNC_/GPIO75_/SPI0_CS2/__Sdio_Dat3_/_UART0_TX_/PWM3_/I2C_SCL1_5") (pintype "passive"))
    )
    (net (code "4") (name "/6") (class "Default")
      (node (ref "P2") (pin "6") (pinfunction "6_6") (pintype "passive"))
      (node (ref "U1") (pin "6") (pinfunction "LCD_EN_/GPIO77_6") (pintype "passive"))
    )
    (net (code "5") (name "/7") (class "Default")
      (node (ref "P2") (pin "7") (pinfunction "7_7") (pintype "passive"))
      (node (ref "U1") (pin "7") (pinfunction "LCD_D0/LCD_B3/GPIO58_/UART4_RX/_UART0_CTS_7") (pintype "passive"))
    )
    (net (code "6") (name "/8") (class "Default")
      (node (ref "P2") (pin "8") (pinfunction "8_8") (pintype "passive"))
      (node (ref "U1") (pin "8") (pinfunction "LCD_D1/LCD_B4/GPIO59_/UART4_TX/_UART0_RTS_8") (pintype "passive"))
    )
    (net (code "7") (name "/9") (class "Default")
      (node (ref "P2") (pin "9") (pinfunction "9_9") (pintype "passive"))
      (node (ref "U1") (pin "9") (pinfunction "LCD_D2/LCD_B5/GPIO60_/UART5_RX/_UART0_DSR_9") (pintype "passive"))
    )
    (net (code "8") (name "/10") (class "Default")
      (node (ref "P2") (pin "10") (pinfunction "10_10") (pintype "passive"))
      (node (ref "U1") (pin "10") (pinfunction "LCD_D3/_LCD_B6_/GPIO61_/UART5_TX/_UART0_DTR_10") (pintype "passive"))
    )
    (net (code "9") (name "/12") (class "Default")
      (node (ref "P2") (pin "12") (pinfunction "12_12") (pintype "passive"))
      (node (ref "U1") (pin "12") (pinfunction "LCD_D4_/LCD_B7_/GPIO62_/UART6_RX/__UART0_DCD_12") (pintype "passive"))
    )
    (net (code "10") (name "/13") (class "Default")
      (node (ref "P2") (pin "13") (pinfunction "13_13") (pintype "passive"))
      (node (ref "U1") (pin "13") (pinfunction "LCD_D5_/LCD_G2_/GPIO63_/UART6_TX/UART0_RI_13") (pintype "passive"))
    )
    (net (code "11") (name "/14") (class "Default")
      (node (ref "P2") (pin "14") (pinfunction "14_14") (pintype "passive"))
      (node (ref "U1") (pin "14") (pinfunction "LCD_D6_/LCD_G3_/GPIO64_/UART7_RX_14") (pintype "passive"))
    )
    (net (code "12") (name "/15") (class "Default")
      (node (ref "P2") (pin "15") (pinfunction "15_15") (pintype "passive"))
      (node (ref "U1") (pin "15") (pinfunction "LCD_D7_/LCD_G4_/GPIO65_/UART7_TX_15") (pintype "passive"))
    )
    (net (code "13") (name "/16") (class "Default")
      (node (ref "P2") (pin "16") (pinfunction "16_16") (pintype "passive"))
      (node (ref "U1") (pin "16") (pinfunction "LCD_D8_/LCD_G5_/GPIO66_/UART8_RX_16") (pintype "passive"))
    )
    (net (code "14") (name "/17") (class "Default")
      (node (ref "P2") (pin "17") (pinfunction "17_17") (pintype "passive"))
      (node (ref "U1") (pin "17") (pinfunction "LCD_D9_/LCD_G6_/GPIO67_/UART8_TX_17") (pintype "passive"))
    )
    (net (code "15") (name "/19") (class "Default")
      (node (ref "P2") (pin "19") (pinfunction "19_19") (pintype "passive"))
      (node (ref "U1") (pin "19") (pinfunction "LCD_D10__/LCD_G7/_GPIO68_/UART9_RX/__UART8_CTS_19") (pintype "passive"))
    )
    (net (code "16") (name "/20") (class "Default")
      (node (ref "P2") (pin "20") (pinfunction "20_20") (pintype "passive"))
      (node (ref "U1") (pin "20") (pinfunction "LCD_R3__/LCD_D11_/GPIO69_/UART9_TX/__UART8_RTS_20") (pintype "passive"))
    )
    (net (code "17") (name "/21") (class "Default")
      (node (ref "P2") (pin "21") (pinfunction "21_21") (pintype "passive"))
      (node (ref "U1") (pin "21") (pinfunction "LCD_D12__/LCD_R4__/GPIO70_/UART10_RX/__UART8_DSR_21") (pintype "passive"))
    )
    (net (code "18") (name "/23") (class "Default")
      (node (ref "P2") (pin "22") (pinfunction "22_22") (pintype "passive"))
      (node (ref "U1") (pin "23") (pinfunction "LCD_D13_/LCD_R5__/GPIO71_/UART10_TX/__UART8_DTR_23") (pintype "passive"))
    )
    (net (code "19") (name "/24") (class "Default")
      (node (ref "P2") (pin "23") (pinfunction "23_23") (pintype "passive"))
      (node (ref "U1") (pin "24") (pinfunction "LCD_D14__/LCD_R6__/GPIO72_/UART11_RX/__UART8_DCD_24") (pintype "passive"))
    )
    (net (code "20") (name "/25") (class "Default")
      (node (ref "P2") (pin "24") (pinfunction "24_24") (pintype "passive"))
      (node (ref "U1") (pin "25") (pinfunction "LCD_D15__/LCD_R7__/GPIO73_/UART11_TX/__UART8_RI_25") (pintype "passive"))
    )
    (net (code "21") (name "/70") (class "Default")
      (node (ref "P5") (pin "2") (pinfunction "2_2") (pintype "passive"))
      (node (ref "U1") (pin "70") (pinfunction "I2S_DI_/GPIO87_/UART7_RX_70") (pintype "passive"))
    )
    (net (code "22") (name "/71") (class "Default")
      (node (ref "P5") (pin "3") (pinfunction "3_3") (pintype "passive"))
      (node (ref "U1") (pin "71") (pinfunction "I2S_DO_/GPIO88_/UART7_TX_71") (pintype "passive"))
    )
    (net (code "23") (name "/72") (class "Default")
      (node (ref "P5") (pin "4") (pinfunction "4_4") (pintype "passive"))
      (node (ref "U1") (pin "72") (pinfunction "I2S_LRCK_/GPIO89_/UART8_RX_72") (pintype "passive"))
    )
    (net (code "24") (name "/73") (class "Default")
      (node (ref "P5") (pin "5") (pinfunction "5_5") (pintype "passive"))
      (node (ref "U1") (pin "73") (pinfunction "I2S_BCLK_/GPIO90_/UART8_TX_73") (pintype "passive"))
    )
    (net (code "25") (name "/74") (class "Default")
      (node (ref "P5") (pin "6") (pinfunction "6_6") (pintype "passive"))
      (node (ref "U1") (pin "74") (pinfunction "I2C_SDA0_/GPIO85_/UART9_RX/__UART8_CTS_74") (pintype "passive"))
    )
    (net (code "26") (name "/75") (class "Default")
      (node (ref "P5") (pin "7") (pinfunction "7_7") (pintype "passive"))
      (node (ref "U1") (pin "75") (pinfunction "I2C_SCL0__/GPIO86_/UART9_TX/__UART8_RTS_75") (pintype "passive"))
    )
    (net (code "27") (name "/76") (class "Default")
      (node (ref "P5") (pin "8") (pinfunction "8_8") (pintype "passive"))
      (node (ref "U1") (pin "76") (pinfunction "I2S_MCLK_/GPIO91_76") (pintype "passive"))
    )
    (net (code "28") (name "/77") (class "Default")
      (node (ref "P5") (pin "9") (pinfunction "9_9") (pintype "passive"))
      (node (ref "U1") (pin "77") (pinfunction "PWM1_/GPIO92_/ADC_YN_77") (pintype "passive"))
    )
    (net (code "29") (name "/78") (class "Default")
      (node (ref "P5") (pin "10") (pinfunction "10_10") (pintype "passive"))
      (node (ref "U1") (pin "78") (pinfunction "PWM0/__CAMCLKOUT__/GPIO06_/ADC_XN_78") (pintype "passive"))
    )
    (net (code "30") (name "/79") (class "Default")
      (node (ref "P5") (pin "11") (pinfunction "11_11") (pintype "passive"))
      (node (ref "U1") (pin "79") (pinfunction "SPI0_CS2_/GPIO83_/Sdio_Dat3_79") (pintype "passive"))
    )
    (net (code "31") (name "/82") (class "Default")
      (node (ref "P5") (pin "14") (pinfunction "14_14") (pintype "passive"))
      (node (ref "U1") (pin "82") (pinfunction "ADC_VREF_82") (pintype "passive"))
    )
    (net (code "32") (name "/85") (class "Default")
      (node (ref "P5") (pin "15") (pinfunction "15_15") (pintype "passive"))
      (node (ref "U1") (pin "85") (pinfunction "ADC_D0_85") (pintype "passive"))
    )
    (net (code "33") (name "/86") (class "Default")
      (node (ref "P5") (pin "16") (pinfunction "16_16") (pintype "passive"))
      (node (ref "U1") (pin "86") (pinfunction "ADC_D1_86") (pintype "passive"))
    )
    (net (code "34") (name "/87") (class "Default")
      (node (ref "P5") (pin "17") (pinfunction "17_17") (pintype "passive"))
      (node (ref "U1") (pin "87") (pinfunction "ADC_XP_87") (pintype "passive"))
    )
    (net (code "35") (name "/88") (class "Default")
      (node (ref "P5") (pin "18") (pinfunction "18_18") (pintype "passive"))
      (node (ref "U1") (pin "88") (pinfunction "ADC_YP_88") (pintype "passive"))
    )
    (net (code "36") (name "/89") (class "Default")
      (node (ref "P5") (pin "19") (pinfunction "19_19") (pintype "passive"))
      (node (ref "U1") (pin "89") (pinfunction "SPI0_CS3_/GPIO84_/CAMCLKOUT_/UART10_RX/__UART8_DSR_89") (pintype "passive"))
    )
    (net (code "37") (name "/93") (class "Default")
      (node (ref "P5") (pin "20") (pinfunction "20_20") (pintype "passive"))
      (node (ref "U1") (pin "93") (pinfunction "SPI0_CS1_/GPIO82_/Sdio_Dat2_/UART10_TX/__UART8_DTR_93") (pintype "passive"))
    )
    (net (code "38") (name "/103") (class "Default")
      (node (ref "P5") (pin "23") (pinfunction "23_23") (pintype "passive"))
      (node (ref "U1") (pin "103") (pinfunction "CAMDATA7_/GPIO57_/LCD_R2_/CAN1_TX_/I2C_SCL2_/UART7_RX_103") (pintype "passive"))
    )
    (net (code "39") (name "/104") (class "Default")
      (node (ref "P5") (pin "24") (pinfunction "24_24") (pintype "passive"))
      (node (ref "U1") (pin "104") (pinfunction "CAMDATA6_/GPIO56_/LCD_R1_/CAN1_RX_/I2C_SDA2_/UART7_TX_104") (pintype "passive"))
    )
    (net (code "40") (name "/105") (class "Default")
      (node (ref "P5") (pin "25") (pinfunction "25_25") (pintype "passive"))
      (node (ref "U1") (pin "105") (pinfunction "CAMDATA5_/GPIO55_/LCD_R0_/CAN0_TX_/I2C_SCL1_/UART8_RX_105") (pintype "passive"))
    )
    (net (code "41") (name "/106") (class "Default")
      (node (ref "P5") (pin "26") (pinfunction "26_26") (pintype "passive"))
      (node (ref "U1") (pin "106") (pinfunction "CAMDATA4_/GPIO54_/LCD_G1_/CAN0_RX_/I2C_SDA1_/UART8_TX_106") (pintype "passive"))
    )
    (net (code "42") (name "/107") (class "Default")
      (node (ref "P5") (pin "27") (pinfunction "27_27") (pintype "passive"))
      (node (ref "U1") (pin "107") (pinfunction "CAMDATA3_/GPIO53_/LCD_G0_/CAMCLKOUT_/PWM3_/UART9_RX/__UART8_CTS_107") (pintype "passive"))
    )
    (net (code "43") (name "/108") (class "Default")
      (node (ref "P5") (pin "28") (pinfunction "28_28") (pintype "passive"))
      (node (ref "U1") (pin "108") (pinfunction "CAMDATA2_/GPIO52_/LCD_B2_/SPI1_CS3_/PWM2_/UART9_TX/__UART8_RTS_108") (pintype "passive"))
    )
    (net (code "44") (name "/109") (class "Default")
      (node (ref "P6") (pin "13") (pinfunction "13_13") (pintype "passive"))
      (node (ref "U1") (pin "109") (pinfunction "CAMDATA1_/GPIO51_/LCD_B1_/SPI1_CS2_/I2C_SCL2_/UART10_RX/__UART8_DSR_109") (pintype "passive"))
    )
    (net (code "45") (name "/110") (class "Default")
      (node (ref "P6") (pin "14") (pinfunction "14_14") (pintype "passive"))
      (node (ref "U1") (pin "110") (pinfunction "CAMDATA0_/GPIO50_/LCD_B0_/SPI1_CS1_/I2C_SDA2_/UART10_TX/__UART8_DTR_110") (pintype "passive"))
    )
    (net (code "46") (name "/112") (class "Default")
      (node (ref "P6") (pin "12") (pinfunction "12_12") (pintype "passive"))
      (node (ref "U1") (pin "112") (pinfunction "CAMHSYNC_/GPIO49_/NAND_RDY3_/SPI1_CS0_/I2C_SCL1_/UART11_RX/__UART8_DCD_112") (pintype "passive"))
    )
    (net (code "47") (name "/113") (class "Default")
      (node (ref "P6") (pin "9") (pinfunction "9_9") (pintype "passive"))
      (node (ref "U1") (pin "113") (pinfunction "CAMVSYNC_/GPIO48_/NAND_CE#3_/SPI1_MOSI_/I2C_SDA1_/UART11_TX/__UART8_RI_113") (pintype "passive"))
    )
    (net (code "48") (name "/114") (class "Default")
      (node (ref "P6") (pin "10") (pinfunction "10_10") (pintype "passive"))
      (node (ref "U1") (pin "114") (pinfunction "CAMCLKOUT_/GPIO47_/SRAM_A25_/NAND_RDY2_/SPI1_MISO_/PWM3_/UART6_RX/__UART0_DCD_114") (pintype "passive"))
    )
    (net (code "49") (name "/115") (class "Default")
      (node (ref "P6") (pin "7") (pinfunction "7_7") (pintype "passive"))
      (node (ref "U1") (pin "115") (pinfunction "CAMPCLKIN_/GPIO46_/SRAM_A24_/NAND_CE#2_/SPI1_CLK_/PWM2_/UART6_TX/__UART0_RI_115") (pintype "passive"))
    )
    (net (code "50") (name "/116") (class "Default")
      (node (ref "P6") (pin "8") (pinfunction "8_8") (pintype "passive"))
      (node (ref "U1") (pin "116") (pinfunction "NAND_7_/GPIO20_/SPI1_CS1/__Sdio_Dat2__/MAC_MDIO_/CAMDATA0_/I2C_SCL2_116") (pintype "passive"))
    )
    (net (code "51") (name "/117") (class "Default")
      (node (ref "P6") (pin "5") (pinfunction "5_5") (pintype "passive"))
      (node (ref "U1") (pin "117") (pinfunction "NAND_6_/GPIO19_/SPI1_CS2/__Sdio_Dat3__/MAC_MDC_/CAMDATA1_/I2C_SDA2_117") (pintype "passive"))
    )
    (net (code "52") (name "/118(5)") (class "Default")
      (node (ref "P6") (pin "6") (pinfunction "6_6") (pintype "passive"))
      (node (ref "R13") (pin "1") (pinfunction "1_1") (pintype "passive"))
      (node (ref "U1") (pin "118") (pinfunction "NAND_5_/GPIO18_/UART1_TX_/UART3_TX_/CAMDATA2_/PWM2_118") (pintype "passive"))
    )
    (net (code "53") (name "/119(4)") (class "Default")
      (node (ref "P6") (pin "3") (pinfunction "3_3") (pintype "passive"))
      (node (ref "R12") (pin "1") (pinfunction "1_1") (pintype "passive"))
      (node (ref "U1") (pin "119") (pinfunction "NAND_4_/GPIO17_/UART1_RX_/UART3_RX_/CAMDATA3_/PWM3_119") (pintype "passive"))
    )
    (net (code "54") (name "/120") (class "Default")
      (node (ref "P6") (pin "4") (pinfunction "4_4") (pintype "passive"))
      (node (ref "U1") (pin "120") (pinfunction "NAND_3_/GPIO16_/SPI1_CS0/__Sdio_Dat1__/CAN1_TX_/CAMDATA4_/I2S_LRCK_120") (pintype "passive"))
    )
    (net (code "55") (name "/121") (class "Default")
      (node (ref "P6") (pin "1") (pinfunction "1_1") (pintype "passive"))
      (node (ref "U1") (pin "121") (pinfunction "NAND_2_/GPIO15_/SPI1_MOSI/__Sdio_Dat0/CAN1_RX_/CAMDATA5_/I2S_DO_121") (pintype "passive"))
    )
    (net (code "56") (name "/122") (class "Default")
      (node (ref "P6") (pin "2") (pinfunction "2_2") (pintype "passive"))
      (node (ref "U1") (pin "122") (pinfunction "NAND_1_/GPIO14_/SPI1_MISO/__Sdio_Cmd__/CAN0_TX_/CAMDATA6_/I2S_BCLK_122") (pintype "passive"))
    )
    (net (code "57") (name "/123") (class "Default")
      (node (ref "P4") (pin "13") (pinfunction "13_13") (pintype "passive"))
      (node (ref "U1") (pin "123") (pinfunction "NAND_0_/GPIO13_/SPI1_CLK/__Sdio_clk__/CAN0_RX_/CAMDATA7_/I2S_MCLK_/GPIO_123") (pintype "passive"))
    )
    (net (code "58") (name "/127") (class "Default")
      (node (ref "P4") (pin "9") (pinfunction "9_9") (pintype "passive"))
      (node (ref "U1") (pin "127") (pinfunction "NAND_RDY_/GPIO07_127") (pintype "passive"))
    )
    (net (code "59") (name "/128") (class "Default")
      (node (ref "P4") (pin "10") (pinfunction "10_10") (pintype "passive"))
      (node (ref "U1") (pin "128") (pinfunction "NAND_CLE_/GPIO08_/GPIO_128") (pintype "passive"))
    )
    (net (code "60") (name "/129") (class "Default")
      (node (ref "P4") (pin "7") (pinfunction "7_7") (pintype "passive"))
      (node (ref "U1") (pin "129") (pinfunction "NAND_ALE_/GPIO09_/GPIO_129") (pintype "passive"))
    )
    (net (code "61") (name "/130") (class "Default")
      (node (ref "P4") (pin "8") (pinfunction "8_8") (pintype "passive"))
      (node (ref "U1") (pin "130") (pinfunction "NAND_RD#_/GPIO10_/GPIO_130") (pintype "passive"))
    )
    (net (code "62") (name "/132") (class "Default")
      (node (ref "P4") (pin "6") (pinfunction "6_6") (pintype "passive"))
      (node (ref "U1") (pin "132") (pinfunction "NAND_CE#_/GPIO11_/GPIO_132") (pintype "passive"))
    )
    (net (code "63") (name "/133") (class "Default")
      (node (ref "P4") (pin "3") (pinfunction "3_3") (pintype "passive"))
      (node (ref "U1") (pin "133") (pinfunction "NAND_WR#_/GPIO12_/GPIO_133") (pintype "passive"))
    )
    (net (code "64") (name "/134") (class "Default")
      (node (ref "P4") (pin "4") (pinfunction "4_4") (pintype "passive"))
      (node (ref "U1") (pin "134") (pinfunction "MAC_TXEN_/GPIO21_/I2S_MCLK_/NAND_CLE_/I2C_SDA2_/CAN0_RX_/UART8_RX_134") (pintype "passive"))
    )
    (net (code "65") (name "/135") (class "Default")
      (node (ref "P4") (pin "1") (pinfunction "1_1") (pintype "passive"))
      (node (ref "U1") (pin "135") (pinfunction "MAC_TXD0_/GPIO23_/I2S_DO_/NAND_ALE_/UART0_RX_/CAN1_RX_/UART4_RX/__UART0_CTS_135") (pintype "passive"))
    )
    (net (code "66") (name "/136") (class "Default")
      (node (ref "P4") (pin "2") (pinfunction "2_2") (pintype "passive"))
      (node (ref "U1") (pin "136") (pinfunction "MAC_TXD1_/GPIO24_/I2S_LRCK_/NAND_WR#_/UART0_TX_/CAN1_TX_/UART4_TX/__UART0_RTS_136") (pintype "passive"))
    )
    (net (code "67") (name "/137") (class "Default")
      (node (ref "P3") (pin "27") (pinfunction "27_27") (pintype "passive"))
      (node (ref "U1") (pin "137") (pinfunction "MAC_RXER_/GPIO25_/I2S_DI_/NAND_RDY0_/I2C_SDA1_/CAMCLKOUT_/UART5_RX/__UART0_DSR_137") (pintype "passive"))
    )
    (net (code "68") (name "/138") (class "Default")
      (node (ref "P3") (pin "28") (pinfunction "28_28") (pintype "passive"))
      (node (ref "U1") (pin "138") (pinfunction "MAC_RXDV_/GPIO26_/SPI1_CS3_/NAND_CE#0_/I2C_SCL1_/CAMPCLKIN_/UART5_TX/__UART0_DTR__/GPIO_138") (pintype "passive"))
    )
    (net (code "69") (name "/139") (class "Default")
      (node (ref "P3") (pin "25") (pinfunction "25_25") (pintype "passive"))
      (node (ref "U1") (pin "139") (pinfunction "MAC_RXD0_/GPIO27_/I2C_SDA_/PWM2_/UART2_RX_/CAMVSYNC_/UART6_RX/__UART0_DCD__/GPIO_139") (pintype "passive"))
    )
    (net (code "70") (name "/140") (class "Default")
      (node (ref "P3") (pin "26") (pinfunction "26_26") (pintype "passive"))
      (node (ref "U1") (pin "140") (pinfunction "MAC_RXD1_/GPIO28_/I2C_SCL_/PWM3_/UART2_TX_/CAMHSYNC_/UART6_TX/__UART0_RI__/GPIO_140") (pintype "passive"))
    )
    (net (code "71") (name "/141") (class "Default")
      (node (ref "P3") (pin "23") (pinfunction "23_23") (pintype "passive"))
      (node (ref "U1") (pin "141") (pinfunction "MAC_MDC_/GPIO29_/CAMDATA7_/NAND_CE#1_/PWM2_/I2C_SCL1_/UART8_TX_/GPIO_141") (pintype "passive"))
    )
    (net (code "72") (name "/143") (class "Default")
      (node (ref "P3") (pin "21") (pinfunction "21_21") (pintype "passive"))
      (node (ref "U1") (pin "143") (pinfunction "MAC_MDIO_/GPIO30_/CAMDATA6_/NAND_RDY1_/LCD_B0_/I2C_SDA1_/GPIO_143") (pintype "passive"))
    )
    (net (code "73") (name "/144") (class "Default")
      (node (ref "P3") (pin "22") (pinfunction "22_22") (pintype "passive"))
      (node (ref "U1") (pin "144") (pinfunction "MAC_RXD2_/GPIO31_/CAMDATA5_/NAND_CS#2_/LCD_B1_/CAN1_RX_/UART11_RX/__UART8_DCD__/GPIO_144") (pintype "passive"))
    )
    (net (code "74") (name "/145") (class "Default")
      (node (ref "D1") (pin "K") (pinfunction "K_K") (pintype "passive"))
      (node (ref "P3") (pin "19") (pinfunction "19_19") (pintype "passive"))
      (node (ref "U1") (pin "145") (pinfunction "MAC_TXD2_/GPIO32_/CAMDATA4_/NAND_RDY2_/LCD_B2_/CAN1_TX_/UART11_TX/__UART8_RI_145") (pintype "passive"))
    )
    (net (code "75") (name "/146") (class "Default")
      (node (ref "P3") (pin "20") (pinfunction "20_20") (pintype "passive"))
      (node (ref "U1") (pin "146") (pinfunction "MAC_RXD3_/GPIO33_/CAMDATA3_/UART3_RX_/LCD_G0_/SPI1_CLK/__Sdio_clk_146") (pintype "passive"))
    )
    (net (code "76") (name "/147") (class "Default")
      (node (ref "P3") (pin "17") (pinfunction "17_17") (pintype "passive"))
      (node (ref "U1") (pin "147") (pinfunction "MAC_TXD3_/GPIO34_/CAMDATA2_/UART3_TX_/LCD_G1_/SPI1_MISO/__Sdio_Cmd_147") (pintype "passive"))
    )
    (net (code "77") (name "/148") (class "Default")
      (node (ref "P3") (pin "18") (pinfunction "18_18") (pintype "passive"))
      (node (ref "U1") (pin "148") (pinfunction "MAC_TXC_/GPIO22_/I2S_BCLK_/NAND_RD#_/I2C_SCL2_/CANO_TX_/SDRAM_CS1_148") (pintype "passive"))
    )
    (net (code "78") (name "/151") (class "Default")
      (node (ref "P3") (pin "13") (pinfunction "13_13") (pintype "passive"))
      (node (ref "U1") (pin "151") (pinfunction "MAC_CRS__(ONLY_MII)_/GPIO35_/CAMDATA1_/PWM1_/LCD_R0_/SPI1_MOSI/__Sdio_Dat0_151") (pintype "passive"))
    )
    (net (code "79") (name "/157") (class "Default")
      (node (ref "P3") (pin "11") (pinfunction "11_11") (pintype "passive"))
      (node (ref "U1") (pin "157") (pinfunction "OTG_DM_157") (pintype "passive"))
    )
    (net (code "80") (name "/158") (class "Default")
      (node (ref "P3") (pin "10") (pinfunction "10_10") (pintype "passive"))
      (node (ref "U1") (pin "158") (pinfunction "OTG_DP_158") (pintype "passive"))
    )
    (net (code "81") (name "/160") (class "Default")
      (node (ref "P3") (pin "8") (pinfunction "8_8") (pintype "passive"))
      (node (ref "U1") (pin "160") (pinfunction "OTG_VBUS_160") (pintype "passive"))
    )
    (net (code "82") (name "/161") (class "Default")
      (node (ref "P3") (pin "7") (pinfunction "7_7") (pintype "passive"))
      (node (ref "U1") (pin "161") (pinfunction "OTG_ID_161") (pintype "passive"))
    )
    (net (code "83") (name "/168") (class "Default")
      (node (ref "P3") (pin "6") (pinfunction "6_6") (pintype "passive"))
      (node (ref "U1") (pin "168") (pinfunction "USB_DM_168") (pintype "passive"))
    )
    (net (code "84") (name "/169") (class "Default")
      (node (ref "P3") (pin "3") (pinfunction "3_3") (pintype "passive"))
      (node (ref "U1") (pin "169") (pinfunction "USB_DP_169") (pintype "passive"))
    )
    (net (code "85") (name "/CH_CLK_SPI0_CLK") (class "Default")
      (node (ref "U5") (pin "18") (pinfunction "D3_18") (pintype "bidirectional"))
      (node (ref "U6") (pin "2") (pinfunction "S1A_2") (pintype "passive"))
    )
    (net (code "86") (name "/CH_MISO_SPI0_MISO") (class "Default")
      (node (ref "U5") (pin "22") (pinfunction "D7_22") (pintype "bidirectional"))
      (node (ref "U6") (pin "11") (pinfunction "S1C_11") (pintype "passive"))
    )
    (net (code "87") (name "/CH_MOSI_SPI0_MOSI") (class "Default")
      (node (ref "U5") (pin "20") (pinfunction "D5_20") (pintype "bidirectional"))
      (node (ref "U6") (pin "5") (pinfunction "S1B_5") (pintype "passive"))
    )
    (net (code "88") (name "/CH_SDA") (class "Default")
      (node (ref "R32") (pin "1") (pinfunction "1_1") (pintype "passive"))
      (node (ref "S1") (pin "2") (pinfunction "2_2") (pintype "passive"))
      (node (ref "U5") (pin "23") (pinfunction "SDA_23") (pintype "bidirectional"))
      (node (ref "U6") (pin "1") (pinfunction "IN_1") (pintype "passive"))
    )
    (net (code "89") (name "/D+") (class "Default")
      (node (ref "J1") (pin "A6") (pinfunction "D+_A6") (pintype "passive"))
      (node (ref "U5") (pin "10") (pinfunction "UD+_10") (pintype "bidirectional"))
    )
    (net (code "90") (name "/D-") (class "Default")
      (node (ref "J1") (pin "A7") (pinfunction "D-_A7") (pintype "passive"))
      (node (ref "U5") (pin "11") (pinfunction "UD-_11") (pintype "bidirectional"))
    )
    (net (code "91") (name "/EJTAG_RST") (class "Default")
      (node (ref "JP1") (pin "1") (pinfunction "1_1") (pintype "passive"))
      (node (ref "R23") (pin "1") (pinfunction "1_1") (pintype "passive"))
      (node (ref "U1") (pin "100") (pinfunction "EJTAG_RST_/GPIO05_/CAMDATA0_/I2C_SCL2_/PWM1_/UART2_TX_/GPIO_100") (pintype "passive"))
    )
    (net (code "92") (name "/EJTAG_SEL") (class "Default")
      (node (ref "R25") (pin "1") (pinfunction "1_1") (pintype "passive"))
      (node (ref "R26") (pin "1") (pinfunction "1_1") (pintype "passive"))
      (node (ref "U1") (pin "95") (pinfunction "EJTAG_SEL_/GPIO00_/CAMCLKOUT_/I2C_SDA0_/CAN0_RX_/UART3_RX_/SDRAM_CS1_/GPIO_95") (pintype "passive"))
    )
    (net (code "93") (name "/EJTAG_TCK") (class "Default")
      (node (ref "JP1") (pin "5") (pinfunction "5_5") (pintype "passive"))
      (node (ref "R6") (pin "2") (pinfunction "2_2") (pintype "passive"))
      (node (ref "U1") (pin "96") (pinfunction "EJTAG_TCK_/GPIO01_/CAMPCLKIN_/I2C_SCL0_/CAN0_TX_/UART3_TX_/GPIO_96") (pintype "passive"))
    )
    (net (code "94") (name "/EJTAG_TDI") (class "Default")
      (node (ref "JP1") (pin "2") (pinfunction "2_2") (pintype "passive"))
      (node (ref "R10") (pin "1") (pinfunction "1_1") (pintype "passive"))
      (node (ref "R9") (pin "1") (pinfunction "1_1") (pintype "passive"))
      (node (ref "U1") (pin "99") (pinfunction "EJTAG_TDI_/GPIO02_/CAMVSYNC_/I2C_SDA1_/CAN1_RX_/UART1_RX_/GPIO_99") (pintype "passive"))
    )
    (net (code "95") (name "/EJTAG_TDO") (class "Default")
      (node (ref "JP1") (pin "3") (pinfunction "3_3") (pintype "passive"))
      (node (ref "R6") (pin "4") (pinfunction "4_4") (pintype "passive"))
      (node (ref "U1") (pin "98") (pinfunction "EJTAG_TDO_/GPIO03_/CAMHSYNC_/I2C_SCL1_/CAN1_TX_/UART1_TX_/GPIO_98") (pintype "passive"))
    )
    (net (code "96") (name "/EJTAG_TMS") (class "Default")
      (node (ref "JP1") (pin "4") (pinfunction "4_4") (pintype "passive"))
      (node (ref "R6") (pin "3") (pinfunction "3_3") (pintype "passive"))
      (node (ref "U1") (pin "97") (pinfunction "EJTAG_TMS_/GPIO04_/CAMDATA1_/I2C_SDA2_/PWM0_/UART2_RX_/GPIO_97") (pintype "passive"))
    )
    (net (code "97") (name "/FLASH_CS0") (class "Default")
      (node (ref "R27") (pin "2") (pinfunction "2_2") (pintype "passive"))
      (node (ref "U3") (pin "1") (pinfunction "~{CS}_1") (pintype "passive"))
      (node (ref "U6") (pin "12") (pinfunction "DD_12") (pintype "passive"))
    )
    (net (code "98") (name "/JTAG_SEL") (class "Default")
      (node (ref "JP1") (pin "6") (pinfunction "6_6") (pintype "passive"))
      (node (ref "R22") (pin "1") (pinfunction "1_1") (pintype "passive"))
      (node (ref "R24") (pin "1") (pinfunction "1_1") (pintype "passive"))
      (node (ref "U1") (pin "126") (pinfunction "JTAG_SEL_/SDRAM_CS1_/UART6_TX/__UART0_RI_126") (pintype "passive"))
    )
    (net (code "99") (name "/RTCI") (class "Default")
      (node (ref "C3") (pin "2") (pinfunction "2_2") (pintype "passive"))
      (node (ref "R1") (pin "1") (pinfunction "1_1") (pintype "passive"))
      (node (ref "U1") (pin "175") (pinfunction "RTC_CLK_I_175") (pintype "passive"))
      (node (ref "X2") (pin "1") (pinfunction "1_1") (pintype "passive"))
    )
    (net (code "100") (name "/RTCO") (class "Default")
      (node (ref "C4") (pin "2") (pinfunction "2_2") (pintype "passive"))
      (node (ref "R1") (pin "2") (pinfunction "2_2") (pintype "passive"))
      (node (ref "U1") (pin "174") (pinfunction "RTC_CLK_O_174") (pintype "passive"))
      (node (ref "X2") (pin "2") (pinfunction "2_2") (pintype "passive"))
    )
    (net (code "101") (name "/RTC_VDDA") (class "Default")
      (node (ref "P3") (pin "4") (pinfunction "4_4") (pintype "passive"))
      (node (ref "U1") (pin "176") (pinfunction "RTC_VR_VDDA_176") (pintype "passive"))
      (node (ref "VD1") (pin "2") (pinfunction "K_2") (pintype "passive"))
    )
    (net (code "102") (name "/SDRAM_A0") (class "Default")
      (node (ref "U1") (pin "67") (pinfunction "SD_A00/__SRAM_A00_67") (pintype "passive"))
      (node (ref "U2") (pin "23") (pinfunction "A0_23") (pintype "passive"))
    )
    (net (code "103") (name "/SDRAM_A1") (class "Default")
      (node (ref "U1") (pin "66") (pinfunction "SD_A01/__SRAM_A01_66") (pintype "passive"))
      (node (ref "U2") (pin "24") (pinfunction "A1_24") (pintype "passive"))
    )
    (net (code "104") (name "/SDRAM_A2") (class "Default")
      (node (ref "U1") (pin "65") (pinfunction "SD_A02/__SRAM_A02_65") (pintype "passive"))
      (node (ref "U2") (pin "25") (pinfunction "A2_25") (pintype "passive"))
    )
    (net (code "105") (name "/SDRAM_A3") (class "Default")
      (node (ref "U1") (pin "64") (pinfunction "SD_A03/__SRAM_A03_64") (pintype "passive"))
      (node (ref "U2") (pin "26") (pinfunction "A3_26") (pintype "passive"))
    )
    (net (code "106") (name "/SDRAM_A4") (class "Default")
      (node (ref "U1") (pin "63") (pinfunction "SD_A04/__SRAM_A04_63") (pintype "passive"))
      (node (ref "U2") (pin "29") (pinfunction "A4_29") (pintype "passive"))
    )
    (net (code "107") (name "/SDRAM_A5") (class "Default")
      (node (ref "U1") (pin "62") (pinfunction "SD_A05/__SRAM_A05_62") (pintype "passive"))
      (node (ref "U2") (pin "30") (pinfunction "A5_30") (pintype "passive"))
    )
    (net (code "108") (name "/SDRAM_A6") (class "Default")
      (node (ref "U1") (pin "61") (pinfunction "SD_A06/__SRAM_A06_61") (pintype "passive"))
      (node (ref "U2") (pin "31") (pinfunction "A6_31") (pintype "passive"))
    )
    (net (code "109") (name "/SDRAM_A7") (class "Default")
      (node (ref "U1") (pin "60") (pinfunction "SD_A07/__SRAM_A07_60") (pintype "passive"))
      (node (ref "U2") (pin "32") (pinfunction "A7_32") (pintype "passive"))
    )
    (net (code "110") (name "/SDRAM_A8") (class "Default")
      (node (ref "U1") (pin "59") (pinfunction "SD_A08/__SRAM_A08_59") (pintype "passive"))
      (node (ref "U2") (pin "33") (pinfunction "A8_33") (pintype "passive"))
    )
    (net (code "111") (name "/SDRAM_A9") (class "Default")
      (node (ref "U1") (pin "58") (pinfunction "SD_A09/__SRAM_A09_58") (pintype "passive"))
      (node (ref "U2") (pin "34") (pinfunction "A9_34") (pintype "passive"))
    )
    (net (code "112") (name "/SDRAM_A10") (class "Default")
      (node (ref "U1") (pin "57") (pinfunction "SD_A10/__SRAM_A10_57") (pintype "passive"))
      (node (ref "U2") (pin "22") (pinfunction "A10_22") (pintype "passive"))
    )
    (net (code "113") (name "/SDRAM_A11") (class "Default")
      (node (ref "U1") (pin "56") (pinfunction "SD_A11/__SRAM_A11_56") (pintype "passive"))
      (node (ref "U2") (pin "35") (pinfunction "A11_35") (pintype "passive"))
    )
    (net (code "114") (name "/SDRAM_A12") (class "Default")
      (node (ref "U1") (pin "55") (pinfunction "SD_A12/__SRAM_A12_55") (pintype "passive"))
      (node (ref "U2") (pin "36") (pinfunction "NC_36") (pintype "passive"))
    )
    (net (code "115") (name "/SDRAM_BA0") (class "Default")
      (node (ref "U1") (pin "52") (pinfunction "SD_BA0/__SRAM_A17_52") (pintype "passive"))
      (node (ref "U2") (pin "20") (pinfunction "BA0_20") (pintype "passive"))
    )
    (net (code "116") (name "/SDRAM_BA1") (class "Default")
      (node (ref "U1") (pin "50") (pinfunction "SD_BA1/__SRAM_A16_50") (pintype "passive"))
      (node (ref "U2") (pin "21") (pinfunction "BA1_21") (pintype "passive"))
    )
    (net (code "117") (name "/SDRAM_CKE") (class "Default")
      (node (ref "U1") (pin "53") (pinfunction "SD_CKE/__SRAM_A13_53") (pintype "passive"))
      (node (ref "U2") (pin "37") (pinfunction "CKE_37") (pintype "passive"))
    )
    (net (code "118") (name "/SDRAM_CLK") (class "Default")
      (node (ref "U1") (pin "54") (pinfunction "SD_CLK/__SRAM_OEn_54") (pintype "passive"))
      (node (ref "U2") (pin "38") (pinfunction "CLK_38") (pintype "passive"))
    )
    (net (code "119") (name "/SDRAM_D0") (class "Default")
      (node (ref "U1") (pin "44") (pinfunction "SD_D00/__SRAM_D00_44") (pintype "passive"))
      (node (ref "U2") (pin "2") (pinfunction "I/O0_2") (pintype "passive"))
    )
    (net (code "120") (name "/SDRAM_D1") (class "Default")
      (node (ref "U1") (pin "43") (pinfunction "SD_D01/__SRAM_D01_43") (pintype "passive"))
      (node (ref "U2") (pin "4") (pinfunction "I/O1_4") (pintype "passive"))
    )
    (net (code "121") (name "/SDRAM_D2") (class "Default")
      (node (ref "U1") (pin "42") (pinfunction "SD_D02/__SRAM_D02_42") (pintype "passive"))
      (node (ref "U2") (pin "5") (pinfunction "I/O2_5") (pintype "passive"))
    )
    (net (code "122") (name "/SDRAM_D3") (class "Default")
      (node (ref "U1") (pin "41") (pinfunction "SD_D03/__SRAM_D03_41") (pintype "passive"))
      (node (ref "U2") (pin "7") (pinfunction "I/O3_7") (pintype "passive"))
    )
    (net (code "123") (name "/SDRAM_D4") (class "Default")
      (node (ref "U1") (pin "40") (pinfunction "SD_D04/__SRAM_D04_40") (pintype "passive"))
      (node (ref "U2") (pin "8") (pinfunction "I/O4_8") (pintype "passive"))
    )
    (net (code "124") (name "/SDRAM_D5") (class "Default")
      (node (ref "U1") (pin "39") (pinfunction "SD_D05/__SRAM_D05_39") (pintype "passive"))
      (node (ref "U2") (pin "10") (pinfunction "I/O5_10") (pintype "passive"))
    )
    (net (code "125") (name "/SDRAM_D6") (class "Default")
      (node (ref "U1") (pin "38") (pinfunction "SD_D06/__SRAM_D06_38") (pintype "passive"))
      (node (ref "U2") (pin "11") (pinfunction "I/O6_11") (pintype "passive"))
    )
    (net (code "126") (name "/SDRAM_D7") (class "Default")
      (node (ref "U1") (pin "37") (pinfunction "SD_D07/__SRAM_D07_37") (pintype "passive"))
      (node (ref "U2") (pin "13") (pinfunction "I/O7_13") (pintype "passive"))
    )
    (net (code "127") (name "/SDRAM_D8") (class "Default")
      (node (ref "U1") (pin "34") (pinfunction "SD_D08/__SRAM_D08_/GPIO97_/I2S_MCLK_/NAND_CLE_/I2C_SDA2_/CAN0_RX_34") (pintype "passive"))
      (node (ref "U2") (pin "42") (pinfunction "I/O8_42") (pintype "passive"))
    )
    (net (code "128") (name "/SDRAM_D9") (class "Default")
      (node (ref "U1") (pin "33") (pinfunction "SD_D09/__SRAM_D09_/GPIO98_/I2S_BCLK_/NAND_RD#_/I2C_SCL2_/CANO_TX_33") (pintype "passive"))
      (node (ref "U2") (pin "44") (pinfunction "I/O9_44") (pintype "passive"))
    )
    (net (code "129") (name "/SDRAM_D10") (class "Default")
      (node (ref "U1") (pin "32") (pinfunction "SD_D10/__SRAM_D10__/GPIO99_/I2S_DI_/NAND_ALE_/UART0_RX_/CAN1_RX_32") (pintype "passive"))
      (node (ref "U2") (pin "45") (pinfunction "I/O10_45") (pintype "passive"))
    )
    (net (code "130") (name "/SDRAM_D11") (class "Default")
      (node (ref "U1") (pin "31") (pinfunction "SD_D11/__SRAM_D11__/GPIO100_/I2S_LRCK_/NAND_WR#_/UART0_TX_/CAN1_TX_31") (pintype "passive"))
      (node (ref "U2") (pin "47") (pinfunction "I/O11_47") (pintype "passive"))
    )
    (net (code "131") (name "/SDRAM_D12") (class "Default")
      (node (ref "U1") (pin "30") (pinfunction "SD_D12/__SRAM_D13/_GPIO101_/UART1_RX_/NAND_RDY_/I2C_SDA1_/PWM0_30") (pintype "passive"))
      (node (ref "U2") (pin "48") (pinfunction "I/O12_48") (pintype "passive"))
    )
    (net (code "132") (name "/SDRAM_D13") (class "Default")
      (node (ref "U1") (pin "29") (pinfunction "SD_D13/__SRAM_D13__/GPIO102_/UART1_TX_/NAND_CE#_/I2C_SCL1_/PWM1_29") (pintype "passive"))
      (node (ref "U2") (pin "50") (pinfunction "I/O13_50") (pintype "passive"))
    )
    (net (code "133") (name "/SDRAM_D14") (class "Default")
      (node (ref "U1") (pin "28") (pinfunction "SD_D14/__SRAM_D14__/GPIO103_/I2C_SDA/_PWM2_/UART2_RX_/MDC_28") (pintype "passive"))
      (node (ref "U2") (pin "51") (pinfunction "I/O14_51") (pintype "passive"))
    )
    (net (code "134") (name "/SDRAM_D15") (class "Default")
      (node (ref "U1") (pin "27") (pinfunction "SD_D15/__SRAM_D15_/GPIO104_/I2C_SCL_/PWM3_/UART2_TX_/MDIO_27") (pintype "passive"))
      (node (ref "U2") (pin "53") (pinfunction "I/O15_53") (pintype "passive"))
    )
    (net (code "135") (name "/SDRAM_DQM0") (class "Default")
      (node (ref "U1") (pin "36") (pinfunction "SD_DQM0/__SRAM_BLEn_36") (pintype "passive"))
      (node (ref "U2") (pin "15") (pinfunction "LDQM_15") (pintype "passive"))
    )
    (net (code "136") (name "/SDRAM_DQM1") (class "Default")
      (node (ref "U1") (pin "35") (pinfunction "SD_DQM1/__SRAM_BHEn__/GPIO96_/I2S_DO_/PWM1_/XTALI_/UART6_RX/__UART0_DCD_35") (pintype "passive"))
      (node (ref "U2") (pin "39") (pinfunction "UDQM_39") (pintype "passive"))
    )
    (net (code "137") (name "/SPI0_CLK") (class "Default")
      (node (ref "R7") (pin "3") (pinfunction "3_3") (pintype "passive"))
      (node (ref "U1") (pin "94") (pinfunction "SPI_CLK_/GPIO78_/Sdio_clk_/UART5_TX/__UART0_DTR_94") (pintype "passive"))
      (node (ref "U6") (pin "3") (pinfunction "S2A_3") (pintype "passive"))
    )
    (net (code "138") (name "/SPI0_CS0") (class "Default")
      (node (ref "U1") (pin "92") (pinfunction "SPI0_CS0_/GPIO81_/Sdio_Dat1_/SDRAM_CS1_/UART5_RX/__UART0_DSR_92") (pintype "passive"))
      (node (ref "U6") (pin "13") (pinfunction "S2D_13") (pintype "passive"))
    )
    (net (code "139") (name "/SPI0_MISO") (class "Default")
      (node (ref "R7") (pin "1") (pinfunction "1_1") (pintype "passive"))
      (node (ref "U1") (pin "90") (pinfunction "SPI0_MISO_/GPIO80_/Sdio_Cmd_/UART4_RX/__UART0_CTS_90") (pintype "passive"))
      (node (ref "U6") (pin "10") (pinfunction "S2C_10") (pintype "passive"))
    )
    (net (code "140") (name "/SPI0_MOSI") (class "Default")
      (node (ref "R7") (pin "2") (pinfunction "2_2") (pintype "passive"))
      (node (ref "U1") (pin "91") (pinfunction "SPI0_MOSI_/GPIO79_/Sdio_Dat0_/UART4_TX/__UART0_RTS_91") (pintype "passive"))
      (node (ref "U6") (pin "6") (pinfunction "S2B_6") (pintype "passive"))
    )
    (net (code "141") (name "/UART2_RX") (class "Default")
      (node (ref "P3") (pin "15") (pinfunction "15_15") (pintype "passive"))
      (node (ref "U1") (pin "149") (pinfunction "MAC_COL_/GPIO36_/CAMDATA0_/UART2_RX_/LCD_R1_/SPI1_CS0/__Sdio_Dat1_149") (pintype "passive"))
      (node (ref "U5") (pin "5") (pinfunction "ERR#_5") (pintype "passive"))
    )
    (net (code "142") (name "/UART2_TX") (class "Default")
      (node (ref "P3") (pin "16") (pinfunction "16_16") (pintype "passive"))
      (node (ref "U1") (pin "150") (pinfunction "MAC_RXC_/GPIO37_/PWM3_/UART2_TX_/LCD_R2_/SPI1_CS1/__Sdio_Dat2_150") (pintype "passive"))
      (node (ref "U5") (pin "6") (pinfunction "PEMP_6") (pintype "passive"))
    )
    (net (code "143") (name "/W_CLK") (class "Default")
      (node (ref "U3") (pin "6") (pinfunction "CLK_6") (pintype "passive"))
      (node (ref "U6") (pin "4") (pinfunction "DA_4") (pintype "passive"))
    )
    (net (code "144") (name "/W_MISO") (class "Default")
      (node (ref "U3") (pin "2") (pinfunction "MISO_2") (pintype "passive"))
      (node (ref "U6") (pin "9") (pinfunction "DC_9") (pintype "passive"))
    )
    (net (code "145") (name "/W_MOSI") (class "Default")
      (node (ref "U3") (pin "5") (pinfunction "MOSI_5") (pintype "passive"))
      (node (ref "U6") (pin "7") (pinfunction "DB_7") (pintype "passive"))
    )
    (net (code "146") (name "/XTALI") (class "Default")
      (node (ref "C1") (pin "2") (pinfunction "2_2") (pintype "passive"))
      (node (ref "R2") (pin "1") (pinfunction "1_1") (pintype "passive"))
      (node (ref "U1") (pin "1") (pinfunction "XTALI_1") (pintype "passive"))
      (node (ref "X1") (pin "1") (pinfunction "1_1") (pintype "passive"))
    )
    (net (code "147") (name "/XTALO") (class "Default")
      (node (ref "C2") (pin "2") (pinfunction "2_2") (pintype "passive"))
      (node (ref "R2") (pin "2") (pinfunction "2_2") (pintype "passive"))
      (node (ref "U1") (pin "2") (pinfunction "XTAL0_2") (pintype "passive"))
      (node (ref "X1") (pin "3") (pinfunction "3_3") (pintype "passive"))
    )
    (net (code "148") (name "/~{CH_CS}") (class "Default")
      (node (ref "U5") (pin "15") (pinfunction "D0_15") (pintype "bidirectional"))
      (node (ref "U6") (pin "14") (pinfunction "S1D_14") (pintype "passive"))
    )
    (net (code "149") (name "/~{SDRAM_CAS}") (class "Default")
      (node (ref "R8") (pin "3") (pinfunction "3_3") (pintype "passive"))
      (node (ref "U1") (pin "47") (pinfunction "SD_CASn/__SRAM_A15_47") (pintype "passive"))
      (node (ref "U2") (pin "17") (pinfunction "~{CAS}_17") (pintype "passive"))
    )
    (net (code "150") (name "/~{SDRAM_CS}") (class "Default")
      (node (ref "R8") (pin "1") (pinfunction "1_1") (pintype "passive"))
      (node (ref "U1") (pin "49") (pinfunction "SD_CSn/__SRAM_CSn_49") (pintype "passive"))
      (node (ref "U2") (pin "19") (pinfunction "~{CS}_19") (pintype "passive"))
    )
    (net (code "151") (name "/~{SDRAM_RAS}") (class "Default")
      (node (ref "R8") (pin "2") (pinfunction "2_2") (pintype "passive"))
      (node (ref "U1") (pin "48") (pinfunction "SD_RASn/__SRAM_A14_48") (pintype "passive"))
      (node (ref "U2") (pin "18") (pinfunction "~{RAS}_18") (pintype "passive"))
    )
    (net (code "152") (name "/~{SDRAM_WE}") (class "Default")
      (node (ref "R8") (pin "4") (pinfunction "4_4") (pintype "passive"))
      (node (ref "U1") (pin "46") (pinfunction "SD_WEn/__SRAM_WEn_46") (pintype "passive"))
      (node (ref "U2") (pin "16") (pinfunction "~{WE}_16") (pintype "passive"))
    )
    (net (code "153") (name "/~{SPI_HOLD}") (class "Default")
      (node (ref "R28") (pin "1") (pinfunction "1_1") (pintype "passive"))
      (node (ref "U3") (pin "7") (pinfunction "~{HOLD}_7") (pintype "passive"))
    )
    (net (code "154") (name "/~{SPI_WP}") (class "Default")
      (node (ref "R29") (pin "2") (pinfunction "2_2") (pintype "passive"))
      (node (ref "U3") (pin "3") (pinfunction "~{WP}_3") (pintype "passive"))
    )
    (net (code "155") (name "/~{SYS_RESET}") (class "Default")
      (node (ref "C32") (pin "2") (pinfunction "2_2") (pintype "passive"))
      (node (ref "P4") (pin "11") (pinfunction "11_11") (pintype "passive"))
      (node (ref "R11") (pin "1") (pinfunction "1_1") (pintype "passive"))
      (node (ref "SW1") (pin "1") (pinfunction "1_1") (pintype "passive"))
      (node (ref "U1") (pin "125") (pinfunction "~{SYS_RST}_125") (pintype "passive"))
    )
    (net (code "156") (name "1V2") (class "Default")
      (node (ref "C20") (pin "2") (pinfunction "2_2") (pintype "passive"))
      (node (ref "C21") (pin "2") (pinfunction "2_2") (pintype "passive"))
      (node (ref "C22") (pin "2") (pinfunction "2_2") (pintype "passive"))
      (node (ref "C23") (pin "2") (pinfunction "2_2") (pintype "passive"))
      (node (ref "C24") (pin "2") (pinfunction "2_2") (pintype "passive"))
      (node (ref "C25") (pin "2") (pinfunction "2_2") (pintype "passive"))
      (node (ref "C26") (pin "2") (pinfunction "2_2") (pintype "passive"))
      (node (ref "C27") (pin "2") (pinfunction "2_2") (pintype "passive"))
      (node (ref "C28") (pin "2") (pinfunction "2_2") (pintype "passive"))
      (node (ref "C29") (pin "2") (pinfunction "2_2") (pintype "passive"))
      (node (ref "C30") (pin "2") (pinfunction "2_2") (pintype "passive"))
      (node (ref "C31") (pin "2") (pinfunction "2_2") (pintype "passive"))
      (node (ref "C56") (pin "1") (pinfunction "1_1") (pintype "passive"))
      (node (ref "L3") (pin "2") (pinfunction "2_2") (pintype "passive"))
      (node (ref "R35") (pin "2") (pinfunction "2_2") (pintype "passive"))
      (node (ref "U1") (pin "101") (pinfunction "CORE_VDD_101") (pintype "passive"))
      (node (ref "U1") (pin "11") (pinfunction "CORE_VDD_11") (pintype "passive"))
      (node (ref "U1") (pin "124") (pinfunction "CORE_VDD_124") (pintype "passive"))
      (node (ref "U1") (pin "152") (pinfunction "CORE_VDD_152") (pintype "passive"))
      (node (ref "U1") (pin "154") (pinfunction "OTG_DVDD_154") (pintype "passive"))
      (node (ref "U1") (pin "164") (pinfunction "USB_DVDD_164") (pintype "passive"))
      (node (ref "U1") (pin "171") (pinfunction "PLL_VDD12_171") (pintype "passive"))
      (node (ref "U1") (pin "26") (pinfunction "CORE_VDD_26") (pintype "passive"))
      (node (ref "U1") (pin "68") (pinfunction "CORE_VDD_68") (pintype "passive"))
    )
    (net (code "157") (name "3V3") (class "Default")
      (node (ref "C10") (pin "2") (pinfunction "2_2") (pintype "passive"))
      (node (ref "C11") (pin "2") (pinfunction "2_2") (pintype "passive"))
      (node (ref "C12") (pin "2") (pinfunction "2_2") (pintype "passive"))
      (node (ref "C13") (pin "2") (pinfunction "2_2") (pintype "passive"))
      (node (ref "C14") (pin "2") (pinfunction "2_2") (pintype "passive"))
      (node (ref "C15") (pin "2") (pinfunction "2_2") (pintype "passive"))
      (node (ref "C16") (pin "2") (pinfunction "2_2") (pintype "passive"))
      (node (ref "C17") (pin "2") (pinfunction "2_2") (pintype "passive"))
      (node (ref "C33") (pin "2") (pinfunction "2_2") (pintype "passive"))
      (node (ref "C34") (pin "2") (pinfunction "2_2") (pintype "passive"))
      (node (ref "C35") (pin "2") (pinfunction "2_2") (pintype "passive"))
      (node (ref "C36") (pin "2") (pinfunction "2_2") (pintype "passive"))
      (node (ref "C37") (pin "2") (pinfunction "2_2") (pintype "passive"))
      (node (ref "C38") (pin "2") (pinfunction "2_2") (pintype "passive"))
      (node (ref "C39") (pin "2") (pinfunction "2_2") (pintype "passive"))
      (node (ref "C40") (pin "2") (pinfunction "2_2") (pintype "passive"))
      (node (ref "C41") (pin "2") (pinfunction "2_2") (pintype "passive"))
      (node (ref "C42") (pin "2") (pinfunction "2_2") (pintype "passive"))
      (node (ref "C43") (pin "2") (pinfunction "2_2") (pintype "passive"))
      (node (ref "C44") (pin "2") (pinfunction "2_2") (pintype "passive"))
      (node (ref "C45") (pin "2") (pinfunction "2_2") (pintype "passive"))
      (node (ref "C46") (pin "2") (pinfunction "2_2") (pintype "passive"))
      (node (ref "C47") (pin "2") (pinfunction "2_2") (pintype "passive"))
      (node (ref "C48") (pin "2") (pinfunction "2_2") (pintype "passive"))
      (node (ref "C49") (pin "2") (pinfunction "2_2") (pintype "passive"))
      (node (ref "C5") (pin "2") (pinfunction "2_2") (pintype "passive"))
      (node (ref "C50") (pin "1") (pinfunction "1_1") (pintype "passive"))
      (node (ref "C52") (pin "2") (pinfunction "2_2") (pintype "passive"))
      (node (ref "C53") (pin "2") (pinfunction "2_2") (pintype "passive"))
      (node (ref "C57") (pin "2") (pinfunction "2_2") (pintype "passive"))
      (node (ref "C6") (pin "2") (pinfunction "2_2") (pintype "passive"))
      (node (ref "C7") (pin "2") (pinfunction "2_2") (pintype "passive"))
      (node (ref "C8") (pin "2") (pinfunction "2_2") (pintype "passive"))
      (node (ref "C9") (pin "2") (pinfunction "2_2") (pintype "passive"))
      (node (ref "L1") (pin "1") (pinfunction "1_1") (pintype "passive"))
      (node (ref "L2") (pin "2") (pinfunction "2_2") (pintype "passive"))
      (node (ref "P2") (pin "27") (pinfunction "27_27") (pintype "passive"))
      (node (ref "P2") (pin "28") (pinfunction "28_28") (pintype "passive"))
      (node (ref "R11") (pin "2") (pinfunction "2_2") (pintype "passive"))
      (node (ref "R12") (pin "2") (pinfunction "2_2") (pintype "passive"))
      (node (ref "R22") (pin "2") (pinfunction "2_2") (pintype "passive"))
      (node (ref "R25") (pin "2") (pinfunction "2_2") (pintype "passive"))
      (node (ref "R27") (pin "1") (pinfunction "1_1") (pintype "passive"))
      (node (ref "R28") (pin "2") (pinfunction "2_2") (pintype "passive"))
      (node (ref "R29") (pin "1") (pinfunction "1_1") (pintype "passive"))
      (node (ref "R31") (pin "2") (pinfunction "2_2") (pintype "passive"))
      (node (ref "R32") (pin "2") (pinfunction "2_2") (pintype "passive"))
      (node (ref "R34") (pin "1") (pinfunction "1_1") (pintype "passive"))
      (node (ref "R37") (pin "1") (pinfunction "1_1") (pintype "passive"))
      (node (ref "R38") (pin "1") (pinfunction "1_1") (pintype "passive"))
      (node (ref "R5") (pin "2") (pinfunction "2_2") (pintype "passive"))
      (node (ref "R6") (pin "5") (pinfunction "5_5") (pintype "passive"))
      (node (ref "R6") (pin "6") (pinfunction "6_6") (pintype "passive"))
      (node (ref "R6") (pin "7") (pinfunction "7_7") (pintype "passive"))
      (node (ref "R7") (pin "6") (pinfunction "6_6") (pintype "passive"))
      (node (ref "R7") (pin "7") (pinfunction "7_7") (pintype "passive"))
      (node (ref "R7") (pin "8") (pinfunction "8_8") (pintype "passive"))
      (node (ref "R8") (pin "5") (pinfunction "5_5") (pintype "passive"))
      (node (ref "R8") (pin "6") (pinfunction "6_6") (pintype "passive"))
      (node (ref "R8") (pin "7") (pinfunction "7_7") (pintype "passive"))
      (node (ref "R8") (pin "8") (pinfunction "8_8") (pintype "passive"))
      (node (ref "R9") (pin "2") (pinfunction "2_2") (pintype "passive"))
      (node (ref "U1") (pin "102") (pinfunction "IO_VDD_102") (pintype "passive"))
      (node (ref "U1") (pin "131") (pinfunction "IO_VDD_131") (pintype "passive"))
      (node (ref "U1") (pin "155") (pinfunction "OTG_VDD33_155") (pintype "passive"))
      (node (ref "U1") (pin "165") (pinfunction "USB_VDD33_165") (pintype "passive"))
      (node (ref "U1") (pin "173") (pinfunction "PLL_VDD33_173") (pintype "passive"))
      (node (ref "U1") (pin "18") (pinfunction "IO_VDD_18") (pintype "passive"))
      (node (ref "U1") (pin "45") (pinfunction "IO_VDD_45") (pintype "passive"))
      (node (ref "U1") (pin "69") (pinfunction "IO_VDD_69") (pintype "passive"))
      (node (ref "U2") (pin "1") (pinfunction "VCC_1") (pintype "passive"))
      (node (ref "U2") (pin "14") (pinfunction "VCC_14") (pintype "passive"))
      (node (ref "U2") (pin "27") (pinfunction "VCC_27") (pintype "passive"))
      (node (ref "U2") (pin "3") (pinfunction "VCCQ_3") (pintype "passive"))
      (node (ref "U2") (pin "43") (pinfunction "VCCQ_43") (pintype "passive"))
      (node (ref "U2") (pin "49") (pinfunction "VCCQ_49") (pintype "passive"))
      (node (ref "U2") (pin "9") (pinfunction "VCCQ_9") (pintype "passive"))
      (node (ref "U3") (pin "8") (pinfunction "VCC_8") (pintype "passive"))
      (node (ref "U5") (pin "28") (pinfunction "VCC_28") (pintype "power_in"))
      (node (ref "U5") (pin "9") (pinfunction "V3_9") (pintype "power_in"))
      (node (ref "U6") (pin "16") (pinfunction "VCC_16") (pintype "passive"))
      (node (ref "U7") (pin "4") (pinfunction "IN_4") (pintype "passive"))
      (node (ref "VD1") (pin "1") (pinfunction "A_1") (pintype "passive"))
    )
    (net (code "158") (name "5V") (class "Default")
      (node (ref "C51") (pin "2") (pinfunction "2_2") (pintype "passive"))
      (node (ref "F1") (pin "2") (pinfunction "2_2") (pintype "passive"))
      (node (ref "U4") (pin "4") (pinfunction "IN_4") (pintype "passive"))
    )
    (net (code "159") (name "5V1") (class "Default")
      (node (ref "F1") (pin "1") (pinfunction "1_1") (pintype "passive"))
      (node (ref "J1") (pin "A4") (pinfunction "VBUS_A4") (pintype "passive"))
      (node (ref "P2") (pin "1") (pinfunction "1_1") (pintype "passive"))
      (node (ref "P3") (pin "1") (pinfunction "1_1") (pintype "passive"))
    )
    (net (code "160") (name "ADC_VDDA") (class "Default")
      (node (ref "C18") (pin "2") (pinfunction "2_2") (pintype "passive"))
      (node (ref "C19") (pin "2") (pinfunction "2_2") (pintype "passive"))
      (node (ref "L1") (pin "2") (pinfunction "2_2") (pintype "passive"))
      (node (ref "U1") (pin "83") (pinfunction "ADC_VDDA_83") (pintype "passive"))
    )
    (net (code "161") (name "GND") (class "Default")
      (node (ref "C1") (pin "1") (pinfunction "1_1") (pintype "passive"))
      (node (ref "C10") (pin "1") (pinfunction "1_1") (pintype "passive"))
      (node (ref "C11") (pin "1") (pinfunction "1_1") (pintype "passive"))
      (node (ref "C12") (pin "1") (pinfunction "1_1") (pintype "passive"))
      (node (ref "C13") (pin "1") (pinfunction "1_1") (pintype "passive"))
      (node (ref "C14") (pin "1") (pinfunction "1_1") (pintype "passive"))
      (node (ref "C15") (pin "1") (pinfunction "1_1") (pintype "passive"))
      (node (ref "C16") (pin "1") (pinfunction "1_1") (pintype "passive"))
      (node (ref "C17") (pin "1") (pinfunction "1_1") (pintype "passive"))
      (node (ref "C18") (pin "1") (pinfunction "1_1") (pintype "passive"))
      (node (ref "C19") (pin "1") (pinfunction "1_1") (pintype "passive"))
      (node (ref "C2") (pin "1") (pinfunction "1_1") (pintype "passive"))
      (node (ref "C20") (pin "1") (pinfunction "1_1") (pintype "passive"))
      (node (ref "C21") (pin "1") (pinfunction "1_1") (pintype "passive"))
      (node (ref "C22") (pin "1") (pinfunction "1_1") (pintype "passive"))
      (node (ref "C23") (pin "1") (pinfunction "1_1") (pintype "passive"))
      (node (ref "C24") (pin "1") (pinfunction "1_1") (pintype "passive"))
      (node (ref "C25") (pin "1") (pinfunction "1_1") (pintype "passive"))
      (node (ref "C26") (pin "1") (pinfunction "1_1") (pintype "passive"))
      (node (ref "C27") (pin "1") (pinfunction "1_1") (pintype "passive"))
      (node (ref "C28") (pin "1") (pinfunction "1_1") (pintype "passive"))
      (node (ref "C29") (pin "1") (pinfunction "1_1") (pintype "passive"))
      (node (ref "C3") (pin "1") (pinfunction "1_1") (pintype "passive"))
      (node (ref "C30") (pin "1") (pinfunction "1_1") (pintype "passive"))
      (node (ref "C31") (pin "1") (pinfunction "1_1") (pintype "passive"))
      (node (ref "C32") (pin "1") (pinfunction "1_1") (pintype "passive"))
      (node (ref "C33") (pin "1") (pinfunction "1_1") (pintype "passive"))
      (node (ref "C34") (pin "1") (pinfunction "1_1") (pintype "passive"))
      (node (ref "C35") (pin "1") (pinfunction "1_1") (pintype "passive"))
      (node (ref "C36") (pin "1") (pinfunction "1_1") (pintype "passive"))
      (node (ref "C37") (pin "1") (pinfunction "1_1") (pintype "passive"))
      (node (ref "C38") (pin "1") (pinfunction "1_1") (pintype "passive"))
      (node (ref "C39") (pin "1") (pinfunction "1_1") (pintype "passive"))
      (node (ref "C4") (pin "1") (pinfunction "1_1") (pintype "passive"))
      (node (ref "C40") (pin "1") (pinfunction "1_1") (pintype "passive"))
      (node (ref "C41") (pin "1") (pinfunction "1_1") (pintype "passive"))
      (node (ref "C42") (pin "1") (pinfunction "1_1") (pintype "passive"))
      (node (ref "C43") (pin "1") (pinfunction "1_1") (pintype "passive"))
      (node (ref "C44") (pin "1") (pinfunction "1_1") (pintype "passive"))
      (node (ref "C45") (pin "1") (pinfunction "1_1") (pintype "passive"))
      (node (ref "C46") (pin "1") (pinfunction "1_1") (pintype "passive"))
      (node (ref "C47") (pin "1") (pinfunction "1_1") (pintype "passive"))
      (node (ref "C48") (pin "1") (pinfunction "1_1") (pintype "passive"))
      (node (ref "C5") (pin "1") (pinfunction "1_1") (pintype "passive"))
      (node (ref "C50") (pin "2") (pinfunction "2_2") (pintype "passive"))
      (node (ref "C51") (pin "1") (pinfunction "1_1") (pintype "passive"))
      (node (ref "C52") (pin "1") (pinfunction "1_1") (pintype "passive"))
      (node (ref "C53") (pin "1") (pinfunction "1_1") (pintype "passive"))
      (node (ref "C54") (pin "1") (pinfunction "1_1") (pintype "passive"))
      (node (ref "C55") (pin "1") (pinfunction "1_1") (pintype "passive"))
      (node (ref "C56") (pin "2") (pinfunction "2_2") (pintype "passive"))
      (node (ref "C57") (pin "1") (pinfunction "1_1") (pintype "passive"))
      (node (ref "C6") (pin "1") (pinfunction "1_1") (pintype "passive"))
      (node (ref "C7") (pin "1") (pinfunction "1_1") (pintype "passive"))
      (node (ref "C8") (pin "1") (pinfunction "1_1") (pintype "passive"))
      (node (ref "C9") (pin "1") (pinfunction "1_1") (pintype "passive"))
      (node (ref "D2") (pin "K") (pinfunction "K_K") (pintype "passive"))
      (node (ref "J1") (pin "A1") (pinfunction "GND_A1") (pintype "passive"))
      (node (ref "J1") (pin "S1") (pinfunction "GND_S1") (pintype "passive"))
      (node (ref "JP1") (pin "7") (pinfunction "7_7") (pintype "passive"))
      (node (ref "P2") (pin "11") (pinfunction "11_11") (pintype "passive"))
      (node (ref "P2") (pin "18") (pinfunction "18_18") (pintype "passive"))
      (node (ref "P2") (pin "2") (pinfunction "2_2") (pintype "passive"))
      (node (ref "P2") (pin "25") (pinfunction "25_25") (pintype "passive"))
      (node (ref "P2") (pin "26") (pinfunction "26_26") (pintype "passive"))
      (node (ref "P3") (pin "12") (pinfunction "12_12") (pintype "passive"))
      (node (ref "P3") (pin "14") (pinfunction "14_14") (pintype "passive"))
      (node (ref "P3") (pin "2") (pinfunction "2_2") (pintype "passive"))
      (node (ref "P3") (pin "24") (pinfunction "24_24") (pintype "passive"))
      (node (ref "P3") (pin "5") (pinfunction "5_5") (pintype "passive"))
      (node (ref "P3") (pin "9") (pinfunction "9_9") (pintype "passive"))
      (node (ref "P4") (pin "12") (pinfunction "12_12") (pintype "passive"))
      (node (ref "P4") (pin "14") (pinfunction "14_14") (pintype "passive"))
      (node (ref "P4") (pin "5") (pinfunction "5_5") (pintype "passive"))
      (node (ref "P5") (pin "1") (pinfunction "1_1") (pintype "passive"))
      (node (ref "P5") (pin "12") (pinfunction "12_12") (pintype "passive"))
      (node (ref "P5") (pin "13") (pinfunction "13_13") (pintype "passive"))
      (node (ref "P5") (pin "21") (pinfunction "21_21") (pintype "passive"))
      (node (ref "P5") (pin "22") (pinfunction "22_22") (pintype "passive"))
      (node (ref "P6") (pin "11") (pinfunction "11_11") (pintype "passive"))
      (node (ref "R10") (pin "2") (pinfunction "2_2") (pintype "passive"))
      (node (ref "R13") (pin "2") (pinfunction "2_2") (pintype "passive"))
      (node (ref "R17") (pin "1") (pinfunction "1_1") (pintype "passive"))
      (node (ref "R23") (pin "2") (pinfunction "2_2") (pintype "passive"))
      (node (ref "R24") (pin "2") (pinfunction "2_2") (pintype "passive"))
      (node (ref "R26") (pin "2") (pinfunction "2_2") (pintype "passive"))
      (node (ref "R3") (pin "1") (pinfunction "1_1") (pintype "passive"))
      (node (ref "R30") (pin "2") (pinfunction "2_2") (pintype "passive"))
      (node (ref "R33") (pin "1") (pinfunction "1_1") (pintype "passive"))
      (node (ref "R36") (pin "1") (pinfunction "1_1") (pintype "passive"))
      (node (ref "R4") (pin "1") (pinfunction "1_1") (pintype "passive"))
      (node (ref "S1") (pin "3") (pinfunction "3_3") (pintype "passive"))
      (node (ref "SW1") (pin "2") (pinfunction "2_2") (pintype "passive"))
      (node (ref "U1") (pin "111") (pinfunction "CORE_VSS_111") (pintype "passive"))
      (node (ref "U1") (pin "142") (pinfunction "CORE_VSS_142") (pintype "passive"))
      (node (ref "U1") (pin "153") (pinfunction "OTG_DVSS_153") (pintype "passive"))
      (node (ref "U1") (pin "156") (pinfunction "OTG_VSS33_156") (pintype "passive"))
      (node (ref "U1") (pin "162") (pinfunction "CORE_VSS_162") (pintype "passive"))
      (node (ref "U1") (pin "163") (pinfunction "USB_DVSS_163") (pintype "passive"))
      (node (ref "U1") (pin "166") (pinfunction "USB_VSS33_166") (pintype "passive"))
      (node (ref "U1") (pin "170") (pinfunction "PLL_VSS12_170") (pintype "passive"))
      (node (ref "U1") (pin "172") (pinfunction "PLL_VSS33_172") (pintype "passive"))
      (node (ref "U1") (pin "22") (pinfunction "CORE_VSS_22") (pintype "passive"))
      (node (ref "U1") (pin "51") (pinfunction "CORE_VSS_51") (pintype "passive"))
      (node (ref "U1") (pin "80") (pinfunction "CORE_VSS_80") (pintype "passive"))
      (node (ref "U1") (pin "84") (pinfunction "ADC_VSSA_84") (pintype "passive"))
      (node (ref "U2") (pin "12") (pinfunction "GNDQ_12") (pintype "passive"))
      (node (ref "U2") (pin "28") (pinfunction "GND_28") (pintype "passive"))
      (node (ref "U2") (pin "41") (pinfunction "GND_41") (pintype "passive"))
      (node (ref "U2") (pin "46") (pinfunction "GNDQ_46") (pintype "passive"))
      (node (ref "U2") (pin "52") (pinfunction "GNDQ_52") (pintype "passive"))
      (node (ref "U2") (pin "54") (pinfunction "GND_54") (pintype "passive"))
      (node (ref "U2") (pin "6") (pinfunction "GNDQ_6") (pintype "passive"))
      (node (ref "U3") (pin "4") (pinfunction "GND_4") (pintype "passive"))
      (node (ref "U4") (pin "2") (pinfunction "GND_2") (pintype "passive"))
      (node (ref "U5") (pin "12") (pinfunction "GND_12") (pintype "power_in"))
      (node (ref "U5") (pin "27") (pinfunction "BUSY_27") (pintype "input"))
      (node (ref "U6") (pin "15") (pinfunction "~{EN}_15") (pintype "passive"))
      (node (ref "U6") (pin "8") (pinfunction "GND_8") (pintype "passive"))
      (node (ref "U7") (pin "2") (pinfunction "GND_2") (pintype "passive"))
      (node (ref "X1") (pin "2") (pinfunction "2_2") (pintype "passive"))
      (node (ref "X1") (pin "4") (pinfunction "4_4") (pintype "passive"))
      (node (ref "X3") (pin "2") (pinfunction "2_2") (pintype "passive"))
      (node (ref "X3") (pin "4") (pinfunction "4_4") (pintype "passive"))
    )
    (net (code "162") (name "Net-(D1-PadA)") (class "Default")
      (node (ref "D1") (pin "A") (pinfunction "A_A") (pintype "passive"))
      (node (ref "R5") (pin "1") (pinfunction "1_1") (pintype "passive"))
    )
    (net (code "163") (name "Net-(D2-PadA)") (class "Default")
      (node (ref "D2") (pin "A") (pinfunction "A_A") (pintype "passive"))
      (node (ref "R38") (pin "2") (pinfunction "2_2") (pintype "passive"))
    )
    (net (code "164") (name "Net-(U1-ADC_REXT)") (class "Default")
      (node (ref "R17") (pin "2") (pinfunction "2_2") (pintype "passive"))
      (node (ref "U1") (pin "81") (pinfunction "ADC_REXT_81") (pintype "passive"))
    )
    (net (code "165") (name "Net-(U1-OTG_REXT)") (class "Default")
      (node (ref "R4") (pin "2") (pinfunction "2_2") (pintype "passive"))
      (node (ref "U1") (pin "159") (pinfunction "OTG_REXT_159") (pintype "passive"))
    )
    (net (code "166") (name "Net-(U1-USB_REXT)") (class "Default")
      (node (ref "R3") (pin "2") (pinfunction "2_2") (pintype "passive"))
      (node (ref "U1") (pin "167") (pinfunction "USB_REXT_167") (pintype "passive"))
    )
    (net (code "167") (name "Net-(U4-EN)") (class "Default")
      (node (ref "R34") (pin "2") (pinfunction "2_2") (pintype "passive"))
      (node (ref "U4") (pin "1") (pinfunction "EN_1") (pintype "passive"))
    )
    (net (code "168") (name "Net-(U4-FB)") (class "Default")
      (node (ref "R31") (pin "1") (pinfunction "1_1") (pintype "passive"))
      (node (ref "R33") (pin "2") (pinfunction "2_2") (pintype "passive"))
      (node (ref "U4") (pin "5") (pinfunction "FB_5") (pintype "passive"))
    )
    (net (code "169") (name "Net-(U4-LX)") (class "Default")
      (node (ref "L2") (pin "1") (pinfunction "1_1") (pintype "passive"))
      (node (ref "U4") (pin "3") (pinfunction "LX_3") (pintype "passive"))
    )
    (net (code "170") (name "Net-(U5-RSTI)") (class "Default")
      (node (ref "C49") (pin "1") (pinfunction "1_1") (pintype "passive"))
      (node (ref "R30") (pin "1") (pinfunction "1_1") (pintype "passive"))
      (node (ref "U5") (pin "2") (pinfunction "RSTI_2") (pintype "passive"))
    )
    (net (code "171") (name "Net-(U5-XI)") (class "Default")
      (node (ref "C55") (pin "2") (pinfunction "2_2") (pintype "passive"))
      (node (ref "U5") (pin "13") (pinfunction "XI_13") (pintype "passive"))
      (node (ref "X3") (pin "1") (pinfunction "1_1") (pintype "passive"))
    )
    (net (code "172") (name "Net-(U5-XO)") (class "Default")
      (node (ref "C54") (pin "2") (pinfunction "2_2") (pintype "passive"))
      (node (ref "U5") (pin "14") (pinfunction "XO_14") (pintype "output"))
      (node (ref "X3") (pin "3") (pinfunction "3_3") (pintype "passive"))
    )
    (net (code "173") (name "Net-(U7-EN)") (class "Default")
      (node (ref "R37") (pin "2") (pinfunction "2_2") (pintype "passive"))
      (node (ref "U7") (pin "1") (pinfunction "EN_1") (pintype "passive"))
    )
    (net (code "174") (name "Net-(U7-FB)") (class "Default")
      (node (ref "R35") (pin "1") (pinfunction "1_1") (pintype "passive"))
      (node (ref "R36") (pin "2") (pinfunction "2_2") (pintype "passive"))
      (node (ref "U7") (pin "5") (pinfunction "FB_5") (pintype "passive"))
    )
    (net (code "175") (name "Net-(U7-LX)") (class "Default")
      (node (ref "L3") (pin "1") (pinfunction "1_1") (pintype "passive"))
      (node (ref "U7") (pin "3") (pinfunction "LX_3") (pintype "passive"))
    )
    (net (code "176") (name "unconnected-(J1-CC1-PadA5)") (class "Default")
      (node (ref "J1") (pin "A5") (pinfunction "CC1_A5") (pintype "passive"))
    )
    (net (code "177") (name "unconnected-(J1-CC2-PadB5)") (class "Default")
      (node (ref "J1") (pin "B5") (pinfunction "CC2_B5") (pintype "passive"))
    )
    (net (code "178") (name "unconnected-(J1-SBU1-PadA8)") (class "Default")
      (node (ref "J1") (pin "A8") (pinfunction "SBU1_A8") (pintype "passive"))
    )
    (net (code "179") (name "unconnected-(J1-SBU2-PadB8)") (class "Default")
      (node (ref "J1") (pin "B8") (pinfunction "SBU2_B8") (pintype "passive"))
    )
    (net (code "180") (name "unconnected-(R6-Pad1)") (class "Default")
      (node (ref "R6") (pin "1") (pinfunction "1_1") (pintype "passive"))
    )
    (net (code "181") (name "unconnected-(R6-Pad8)") (class "Default")
      (node (ref "R6") (pin "8") (pinfunction "8_8") (pintype "passive"))
    )
    (net (code "182") (name "unconnected-(R7-Pad4)") (class "Default")
      (node (ref "R7") (pin "4") (pinfunction "4_4") (pintype "passive"))
    )
    (net (code "183") (name "unconnected-(R7-Pad5)") (class "Default")
      (node (ref "R7") (pin "5") (pinfunction "5_5") (pintype "passive"))
    )
    (net (code "184") (name "unconnected-(S1-Pad1)") (class "Default")
      (node (ref "S1") (pin "1") (pinfunction "1_1") (pintype "passive"))
    )
    (net (code "185") (name "unconnected-(U2-NC-Pad40)") (class "Default")
      (node (ref "U2") (pin "40") (pinfunction "NC_40") (pintype "passive"))
    )
    (net (code "186") (name "unconnected-(U5-ACK#-Pad7)") (class "Default")
      (node (ref "U5") (pin "7") (pinfunction "ACK#_7") (pintype "passive"))
    )
    (net (code "187") (name "unconnected-(U5-ACT#-Pad1)") (class "Default")
      (node (ref "U5") (pin "1") (pinfunction "ACT#_1") (pintype "output"))
    )
    (net (code "188") (name "unconnected-(U5-AFD#-Pad4)") (class "Default")
      (node (ref "U5") (pin "4") (pinfunction "AFD#_4") (pintype "output"))
    )
    (net (code "189") (name "unconnected-(U5-D1-Pad16)") (class "Default")
      (node (ref "U5") (pin "16") (pinfunction "D1_16") (pintype "bidirectional"))
    )
    (net (code "190") (name "unconnected-(U5-D2-Pad17)") (class "Default")
      (node (ref "U5") (pin "17") (pinfunction "D2_17") (pintype "bidirectional"))
    )
    (net (code "191") (name "unconnected-(U5-D4-Pad19)") (class "Default")
      (node (ref "U5") (pin "19") (pinfunction "D4_19") (pintype "bidirectional"))
    )
    (net (code "192") (name "unconnected-(U5-D6-Pad21)") (class "Default")
      (node (ref "U5") (pin "21") (pinfunction "D6_21") (pintype "bidirectional"))
    )
    (net (code "193") (name "unconnected-(U5-INI#-Pad26)") (class "Default")
      (node (ref "U5") (pin "26") (pinfunction "INI#_26") (pintype "output"))
    )
    (net (code "194") (name "unconnected-(U5-SCL-Pad24)") (class "Default")
      (node (ref "U5") (pin "24") (pinfunction "SCL_24") (pintype "output"))
    )
    (net (code "195") (name "unconnected-(U5-SIN#-Pad3)") (class "Default")
      (node (ref "U5") (pin "3") (pinfunction "SIN#_3") (pintype "output"))
    )
    (net (code "196") (name "unconnected-(U5-SLCT-Pad8)") (class "Default")
      (node (ref "U5") (pin "8") (pinfunction "SLCT_8") (pintype "passive"))
    )
    (net (code "197") (name "unconnected-(U5-STB#-Pad25)") (class "Default")
      (node (ref "U5") (pin "25") (pinfunction "STB#_25") (pintype "output"))
    )
  )
)
